# Magus.net
KiCad netlist of a schematic drawn in EAGLE
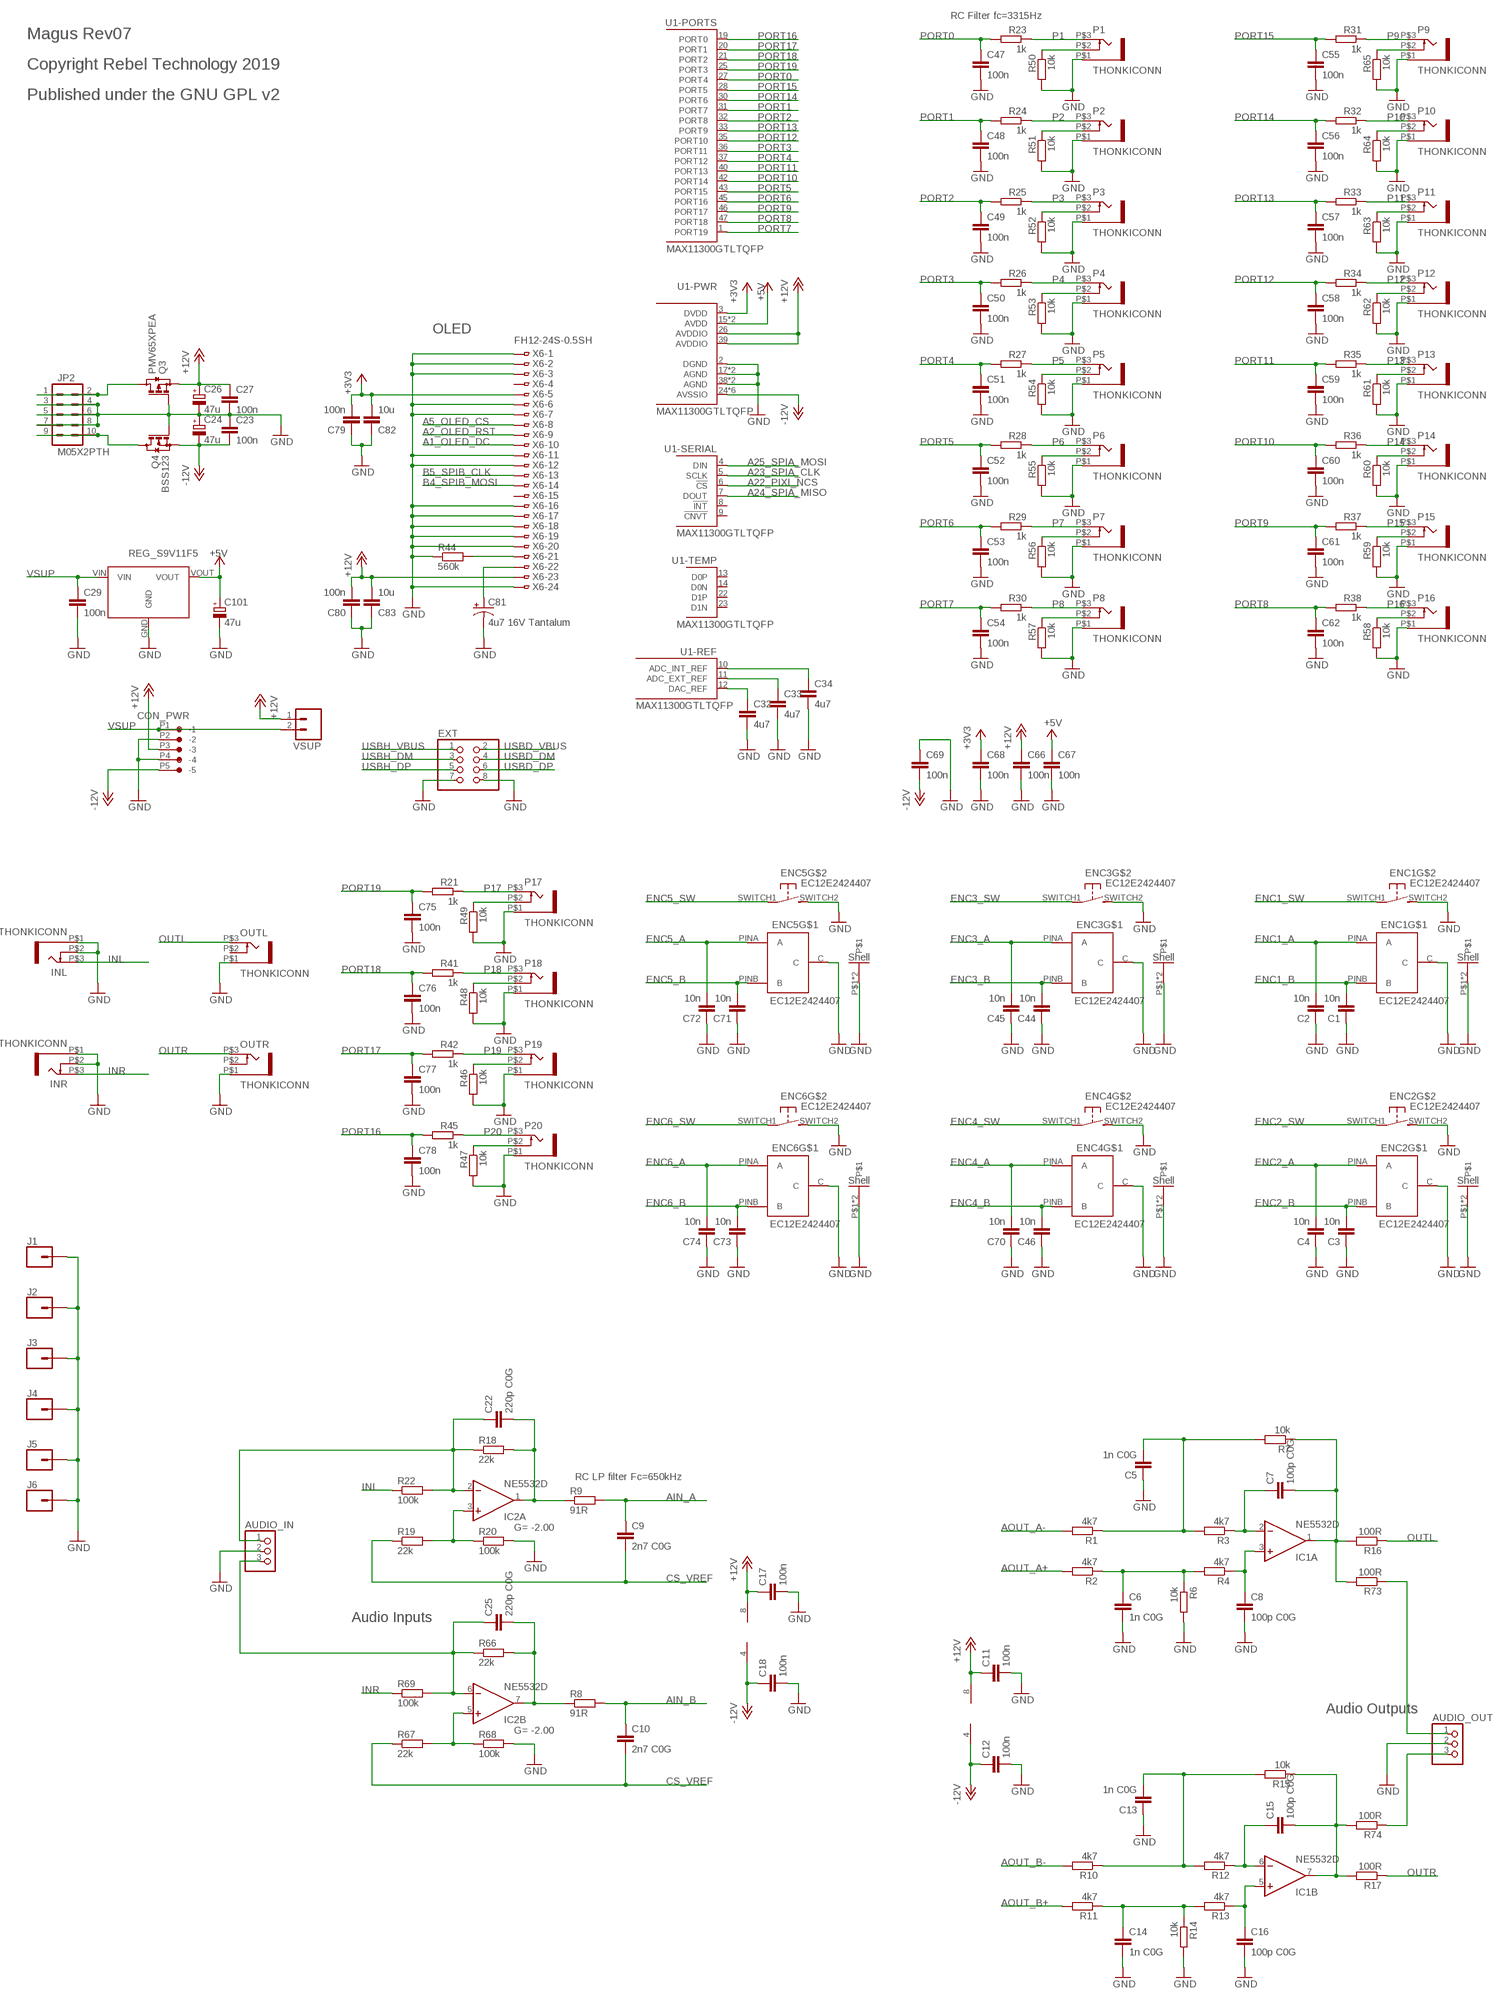
[diagram p0: schematic, sheet 1, part 1 of 2]
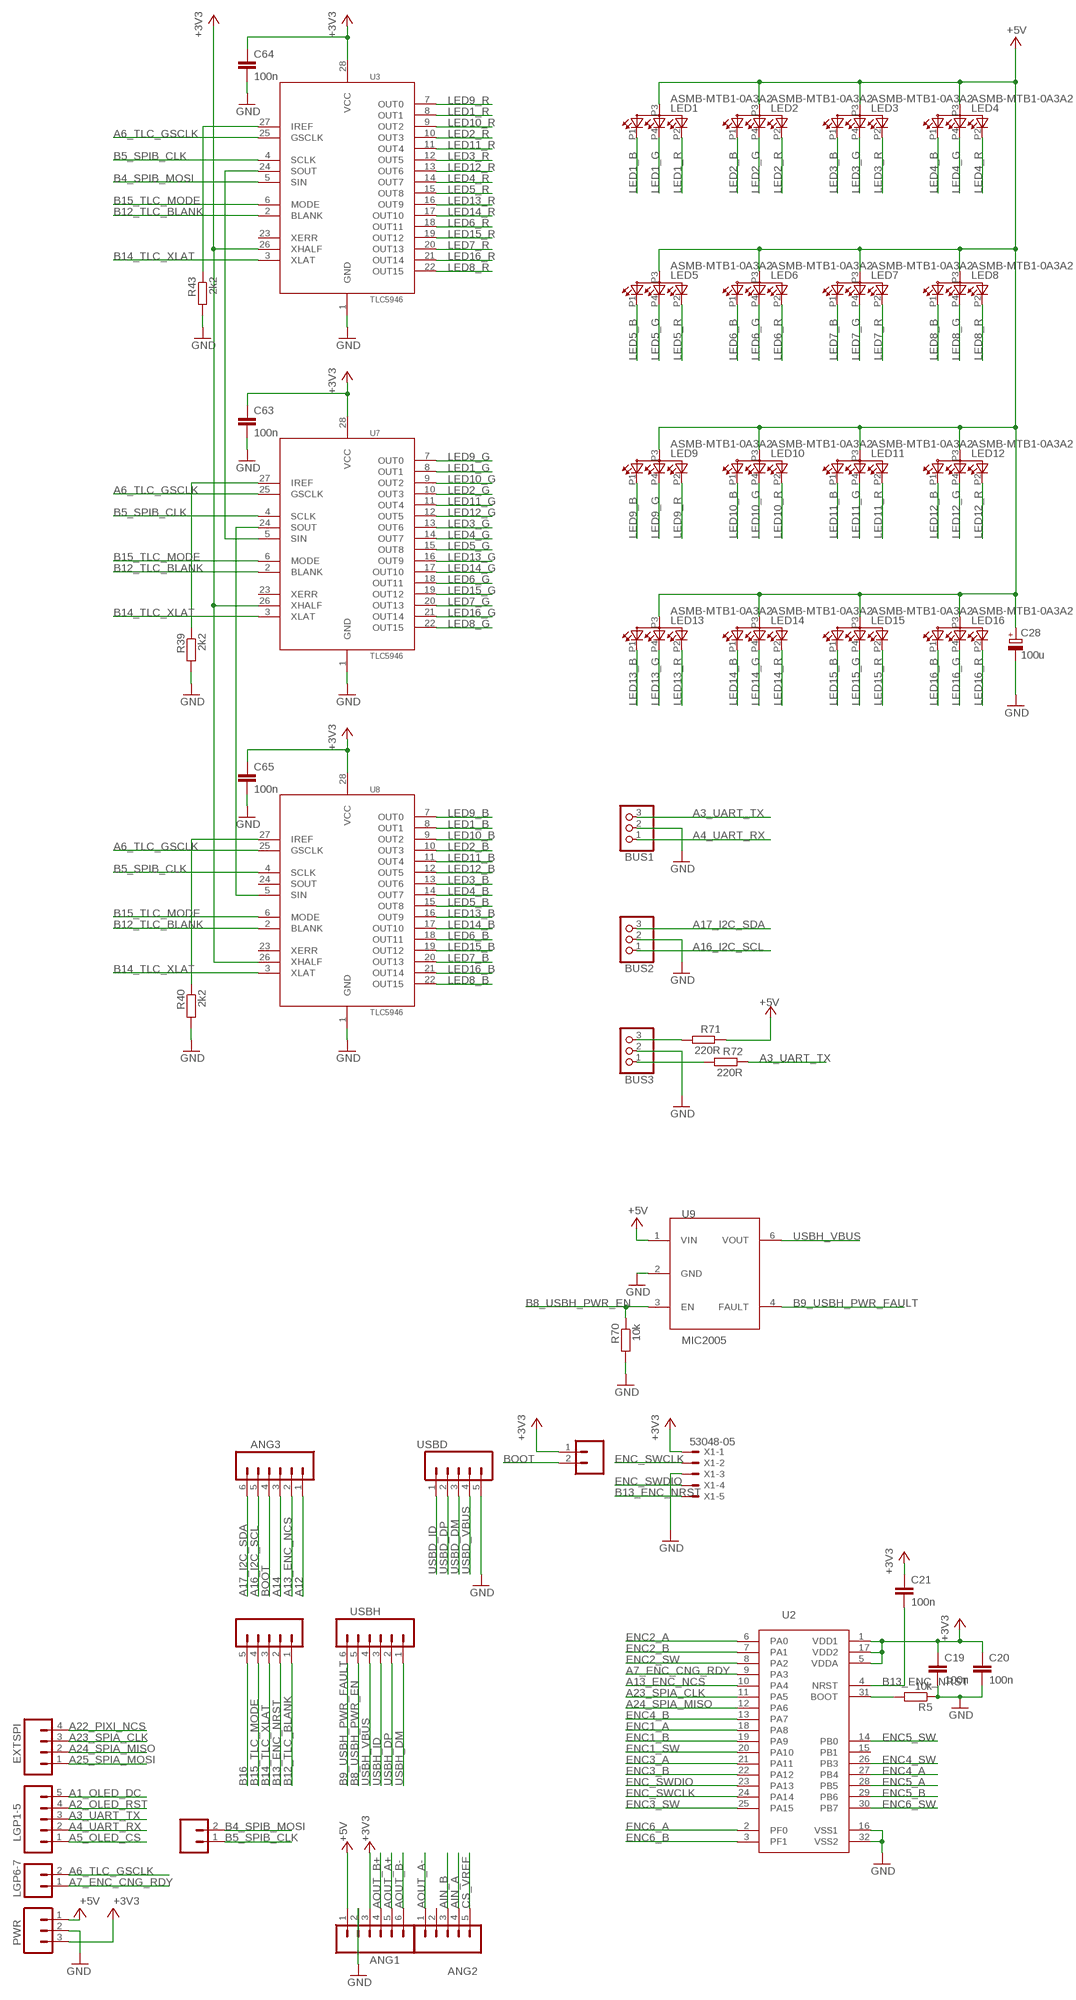
[diagram p1: schematic, sheet 1, part 2 of 2]

(export (version "E")
  (design (tool "Eeschema 10.0.6"))
  (components
    (comp (ref "ANG1")
      (value "M06SIP")
      (footprint "eagle-import:1X06")
      (libsource (lib "eagle-import") (part "M06SIP"))
    )
    (comp (ref "ANG2")
      (value "M05PTH")
      (footprint "eagle-import:1X05")
      (libsource (lib "eagle-import") (part "M05PTH"))
    )
    (comp (ref "ANG3")
      (value "M06SIP")
      (footprint "eagle-import:1X06")
      (libsource (lib "eagle-import") (part "M06SIP"))
    )
    (comp (ref "AUDIO_IN")
      (value "CON-JST-1X03PH-TH")
      (footprint "eagle-import:JST-B3B-PH-KL")
      (libsource (lib "eagle-import") (part "CON-JST-1X03PH-TH"))
    )
    (comp (ref "AUDIO_OUT")
      (value "CON-JST-1X03PH-TH")
      (footprint "eagle-import:JST-B3B-PH-KL")
      (libsource (lib "eagle-import") (part "CON-JST-1X03PH-TH"))
    )
    (comp (ref "BOOT")
      (value "M02PTH")
      (footprint "eagle-import:1X02")
      (libsource (lib "eagle-import") (part "M02PTH"))
    )
    (comp (ref "BUS1")
      (value "CON-JST-1X03PH-TH")
      (footprint "eagle-import:JST-B3B-PH-KL")
      (libsource (lib "eagle-import") (part "CON-JST-1X03PH-TH"))
    )
    (comp (ref "BUS2")
      (value "CON-JST-1X03PH-TH")
      (footprint "eagle-import:JST-B3B-PH-KL")
      (libsource (lib "eagle-import") (part "CON-JST-1X03PH-TH"))
    )
    (comp (ref "BUS3")
      (value "CON-JST-1X03PH-TH")
      (footprint "eagle-import:JST-B3B-PH-KL")
      (libsource (lib "eagle-import") (part "CON-JST-1X03PH-TH"))
    )
    (comp (ref "C1")
      (value "10n")
      (footprint "eagle-import:C0603")
      (libsource (lib "eagle-import") (part "C-EUC0603"))
    )
    (comp (ref "C2")
      (value "10n")
      (footprint "eagle-import:C0603")
      (libsource (lib "eagle-import") (part "C-EUC0603"))
    )
    (comp (ref "C3")
      (value "10n")
      (footprint "eagle-import:C0603")
      (libsource (lib "eagle-import") (part "C-EUC0603"))
    )
    (comp (ref "C4")
      (value "10n")
      (footprint "eagle-import:C0603")
      (libsource (lib "eagle-import") (part "C-EUC0603"))
    )
    (comp (ref "C5")
      (value "1n C0G")
      (footprint "eagle-import:C0603")
      (libsource (lib "eagle-import") (part "C-EUC0603"))
    )
    (comp (ref "C6")
      (value "1n C0G")
      (footprint "eagle-import:C0603")
      (libsource (lib "eagle-import") (part "C-EUC0603"))
    )
    (comp (ref "C7")
      (value "100p C0G")
      (footprint "eagle-import:C0603")
      (libsource (lib "eagle-import") (part "C-EUC0603"))
    )
    (comp (ref "C8")
      (value "100p C0G")
      (footprint "eagle-import:C0603")
      (libsource (lib "eagle-import") (part "C-EUC0603"))
    )
    (comp (ref "C9")
      (value "2n7 C0G")
      (footprint "eagle-import:C0603")
      (libsource (lib "eagle-import") (part "C-EUC0603"))
    )
    (comp (ref "C10")
      (value "2n7 C0G")
      (footprint "eagle-import:C0603")
      (libsource (lib "eagle-import") (part "C-EUC0603"))
    )
    (comp (ref "C11")
      (value "100n")
      (footprint "eagle-import:C0603")
      (libsource (lib "eagle-import") (part "C-EUC0603"))
    )
    (comp (ref "C12")
      (value "100n")
      (footprint "eagle-import:C0603")
      (libsource (lib "eagle-import") (part "C-EUC0603"))
    )
    (comp (ref "C13")
      (value "1n C0G")
      (footprint "eagle-import:C0603")
      (libsource (lib "eagle-import") (part "C-EUC0603"))
    )
    (comp (ref "C14")
      (value "1n C0G")
      (footprint "eagle-import:C0603")
      (libsource (lib "eagle-import") (part "C-EUC0603"))
    )
    (comp (ref "C15")
      (value "100p C0G")
      (footprint "eagle-import:C0603")
      (libsource (lib "eagle-import") (part "C-EUC0603"))
    )
    (comp (ref "C16")
      (value "100p C0G")
      (footprint "eagle-import:C0603")
      (libsource (lib "eagle-import") (part "C-EUC0603"))
    )
    (comp (ref "C17")
      (value "100n")
      (footprint "eagle-import:C0603")
      (libsource (lib "eagle-import") (part "C-EUC0603"))
    )
    (comp (ref "C18")
      (value "100n")
      (footprint "eagle-import:C0603")
      (libsource (lib "eagle-import") (part "C-EUC0603"))
    )
    (comp (ref "C19")
      (value "100n")
      (footprint "eagle-import:C0603")
      (libsource (lib "eagle-import") (part "C-EUC0603"))
    )
    (comp (ref "C20")
      (value "100n")
      (footprint "eagle-import:C0603")
      (libsource (lib "eagle-import") (part "C-EUC0603"))
    )
    (comp (ref "C21")
      (value "100n")
      (footprint "eagle-import:C0603")
      (libsource (lib "eagle-import") (part "C-EUC0603"))
    )
    (comp (ref "C22")
      (value "220p C0G")
      (footprint "eagle-import:C0603")
      (libsource (lib "eagle-import") (part "C-EUC0603"))
    )
    (comp (ref "C23")
      (value "100n")
      (footprint "eagle-import:C0603")
      (libsource (lib "eagle-import") (part "C-EUC0603"))
    )
    (comp (ref "C24")
      (value "47u")
      (footprint "eagle-import:CPOL-5")
      (libsource (lib "eagle-import") (part "CPOL-EU153CLV-0505"))
    )
    (comp (ref "C25")
      (value "220p C0G")
      (footprint "eagle-import:C0603")
      (libsource (lib "eagle-import") (part "C-EUC0603"))
    )
    (comp (ref "C26")
      (value "47u")
      (footprint "eagle-import:CPOL-5")
      (libsource (lib "eagle-import") (part "CPOL-EU153CLV-0505"))
    )
    (comp (ref "C27")
      (value "100n")
      (footprint "eagle-import:C0603")
      (libsource (lib "eagle-import") (part "C-EUC0603"))
    )
    (comp (ref "C28")
      (value "100u")
      (footprint "eagle-import:E5-8,5")
      (libsource (lib "eagle-import") (part "CPOL-EUE5-8.5"))
    )
    (comp (ref "C29")
      (value "100n")
      (footprint "eagle-import:C0603")
      (libsource (lib "eagle-import") (part "C-EUC0603"))
    )
    (comp (ref "C32")
      (value "4u7")
      (footprint "eagle-import:C0603")
      (libsource (lib "eagle-import") (part "C-EUC0603"))
    )
    (comp (ref "C33")
      (value "4u7")
      (footprint "eagle-import:C0603")
      (libsource (lib "eagle-import") (part "C-EUC0603"))
    )
    (comp (ref "C34")
      (value "4u7")
      (footprint "eagle-import:C0603")
      (libsource (lib "eagle-import") (part "C-EUC0603"))
    )
    (comp (ref "C44")
      (value "10n")
      (footprint "eagle-import:C0603")
      (libsource (lib "eagle-import") (part "C-EUC0603"))
    )
    (comp (ref "C45")
      (value "10n")
      (footprint "eagle-import:C0603")
      (libsource (lib "eagle-import") (part "C-EUC0603"))
    )
    (comp (ref "C46")
      (value "10n")
      (footprint "eagle-import:C0603")
      (libsource (lib "eagle-import") (part "C-EUC0603"))
    )
    (comp (ref "C47")
      (value "100n")
      (footprint "eagle-import:C0603")
      (libsource (lib "eagle-import") (part "C-EUC0603"))
    )
    (comp (ref "C48")
      (value "100n")
      (footprint "eagle-import:C0603")
      (libsource (lib "eagle-import") (part "C-EUC0603"))
    )
    (comp (ref "C49")
      (value "100n")
      (footprint "eagle-import:C0603")
      (libsource (lib "eagle-import") (part "C-EUC0603"))
    )
    (comp (ref "C50")
      (value "100n")
      (footprint "eagle-import:C0603")
      (libsource (lib "eagle-import") (part "C-EUC0603"))
    )
    (comp (ref "C51")
      (value "100n")
      (footprint "eagle-import:C0603")
      (libsource (lib "eagle-import") (part "C-EUC0603"))
    )
    (comp (ref "C52")
      (value "100n")
      (footprint "eagle-import:C0603")
      (libsource (lib "eagle-import") (part "C-EUC0603"))
    )
    (comp (ref "C53")
      (value "100n")
      (footprint "eagle-import:C0603")
      (libsource (lib "eagle-import") (part "C-EUC0603"))
    )
    (comp (ref "C54")
      (value "100n")
      (footprint "eagle-import:C0603")
      (libsource (lib "eagle-import") (part "C-EUC0603"))
    )
    (comp (ref "C55")
      (value "100n")
      (footprint "eagle-import:C0603")
      (libsource (lib "eagle-import") (part "C-EUC0603"))
    )
    (comp (ref "C56")
      (value "100n")
      (footprint "eagle-import:C0603")
      (libsource (lib "eagle-import") (part "C-EUC0603"))
    )
    (comp (ref "C57")
      (value "100n")
      (footprint "eagle-import:C0603")
      (libsource (lib "eagle-import") (part "C-EUC0603"))
    )
    (comp (ref "C58")
      (value "100n")
      (footprint "eagle-import:C0603")
      (libsource (lib "eagle-import") (part "C-EUC0603"))
    )
    (comp (ref "C59")
      (value "100n")
      (footprint "eagle-import:C0603")
      (libsource (lib "eagle-import") (part "C-EUC0603"))
    )
    (comp (ref "C60")
      (value "100n")
      (footprint "eagle-import:C0603")
      (libsource (lib "eagle-import") (part "C-EUC0603"))
    )
    (comp (ref "C61")
      (value "100n")
      (footprint "eagle-import:C0603")
      (libsource (lib "eagle-import") (part "C-EUC0603"))
    )
    (comp (ref "C62")
      (value "100n")
      (footprint "eagle-import:C0603")
      (libsource (lib "eagle-import") (part "C-EUC0603"))
    )
    (comp (ref "C63")
      (value "100n")
      (footprint "eagle-import:C0603")
      (libsource (lib "eagle-import") (part "C-EUC0603"))
    )
    (comp (ref "C64")
      (value "100n")
      (footprint "eagle-import:C0603")
      (libsource (lib "eagle-import") (part "C-EUC0603"))
    )
    (comp (ref "C65")
      (value "100n")
      (footprint "eagle-import:C0603")
      (libsource (lib "eagle-import") (part "C-EUC0603"))
    )
    (comp (ref "C66")
      (value "100n")
      (footprint "eagle-import:C0603")
      (libsource (lib "eagle-import") (part "C-EUC0603"))
    )
    (comp (ref "C67")
      (value "100n")
      (footprint "eagle-import:C0603")
      (libsource (lib "eagle-import") (part "C-EUC0603"))
    )
    (comp (ref "C68")
      (value "100n")
      (footprint "eagle-import:C0603")
      (libsource (lib "eagle-import") (part "C-EUC0603"))
    )
    (comp (ref "C69")
      (value "100n")
      (footprint "eagle-import:C0603")
      (libsource (lib "eagle-import") (part "C-EUC0603"))
    )
    (comp (ref "C70")
      (value "10n")
      (footprint "eagle-import:C0603")
      (libsource (lib "eagle-import") (part "C-EUC0603"))
    )
    (comp (ref "C71")
      (value "10n")
      (footprint "eagle-import:C0603")
      (libsource (lib "eagle-import") (part "C-EUC0603"))
    )
    (comp (ref "C72")
      (value "10n")
      (footprint "eagle-import:C0603")
      (libsource (lib "eagle-import") (part "C-EUC0603"))
    )
    (comp (ref "C73")
      (value "10n")
      (footprint "eagle-import:C0603")
      (libsource (lib "eagle-import") (part "C-EUC0603"))
    )
    (comp (ref "C74")
      (value "10n")
      (footprint "eagle-import:C0603")
      (libsource (lib "eagle-import") (part "C-EUC0603"))
    )
    (comp (ref "C75")
      (value "100n")
      (footprint "eagle-import:C0603")
      (libsource (lib "eagle-import") (part "C-EUC0603"))
    )
    (comp (ref "C76")
      (value "100n")
      (footprint "eagle-import:C0603")
      (libsource (lib "eagle-import") (part "C-EUC0603"))
    )
    (comp (ref "C77")
      (value "100n")
      (footprint "eagle-import:C0603")
      (libsource (lib "eagle-import") (part "C-EUC0603"))
    )
    (comp (ref "C78")
      (value "100n")
      (footprint "eagle-import:C0603")
      (libsource (lib "eagle-import") (part "C-EUC0603"))
    )
    (comp (ref "C79")
      (value "100n")
      (footprint "eagle-import:C0603")
      (libsource (lib "eagle-import") (part "C-EUC0603"))
    )
    (comp (ref "C80")
      (value "100n")
      (footprint "eagle-import:C0603")
      (libsource (lib "eagle-import") (part "C-EUC0603"))
    )
    (comp (ref "C81")
      (value "4u7 16V Tantalum")
      (footprint "eagle-import:EIA3216")
      (libsource (lib "eagle-import") (part "CAP_POL1206"))
    )
    (comp (ref "C82")
      (value "10u")
      (footprint "eagle-import:C1206")
      (libsource (lib "eagle-import") (part "C-EUC1206"))
    )
    (comp (ref "C83")
      (value "10u")
      (footprint "eagle-import:C1206")
      (libsource (lib "eagle-import") (part "C-EUC1206"))
    )
    (comp (ref "C101")
      (value "47u")
      (footprint "eagle-import:CPOL-5")
      (libsource (lib "eagle-import") (part "CPOL-EU153CLV-0505"))
    )
    (comp (ref "CON_PWR")
      (value "CON-JST_PH_5W")
      (footprint "eagle-import:CON-JST_PH_5W")
      (libsource (lib "eagle-import") (part "CON-JST_PH_5W"))
    )
    (comp (ref "ENC1")
      (value "EC12E2424407")
      (footprint "eagle-import:EC12E2424407")
      (libsource (lib "eagle-import") (part "EC12E2424407"))
    )
    (comp (ref "ENC2")
      (value "EC12E2424407")
      (footprint "eagle-import:EC12E2424407")
      (libsource (lib "eagle-import") (part "EC12E2424407"))
    )
    (comp (ref "ENC3")
      (value "EC12E2424407")
      (footprint "eagle-import:EC12E2424407")
      (libsource (lib "eagle-import") (part "EC12E2424407"))
    )
    (comp (ref "ENC4")
      (value "EC12E2424407")
      (footprint "eagle-import:EC12E2424407")
      (libsource (lib "eagle-import") (part "EC12E2424407"))
    )
    (comp (ref "ENC5")
      (value "EC12E2424407")
      (footprint "eagle-import:EC12E2424407")
      (libsource (lib "eagle-import") (part "EC12E2424407"))
    )
    (comp (ref "ENC6")
      (value "EC12E2424407")
      (footprint "eagle-import:EC12E2424407")
      (libsource (lib "eagle-import") (part "EC12E2424407"))
    )
    (comp (ref "EXT")
      (value "PINHD-2X4")
      (footprint "eagle-import:2X04")
      (libsource (lib "eagle-import") (part "PINHD-2X4"))
    )
    (comp (ref "EXTSPI")
      (value "M04PTH")
      (footprint "eagle-import:1X04")
      (libsource (lib "eagle-import") (part "M04PTH"))
    )
    (comp (ref "IC1")
      (value "NE5532D")
      (footprint "eagle-import:SO08")
      (libsource (lib "eagle-import") (part "NE5532D"))
    )
    (comp (ref "IC2")
      (value "NE5532D")
      (footprint "eagle-import:SO08")
      (libsource (lib "eagle-import") (part "NE5532D"))
    )
    (comp (ref "INL")
      (value "THONKICONN")
      (footprint "eagle-import:THONKICONN")
      (libsource (lib "eagle-import") (part "THONKICONN"))
    )
    (comp (ref "INR")
      (value "THONKICONN")
      (footprint "eagle-import:THONKICONN")
      (libsource (lib "eagle-import") (part "THONKICONN"))
    )
    (comp (ref "J1")
      (value "CONN_01")
      (footprint "eagle-import:1X01")
      (libsource (lib "eagle-import") (part "CONN_01"))
    )
    (comp (ref "J2")
      (value "CONN_01")
      (footprint "eagle-import:1X01")
      (libsource (lib "eagle-import") (part "CONN_01"))
    )
    (comp (ref "J3")
      (value "CONN_01")
      (footprint "eagle-import:1X01")
      (libsource (lib "eagle-import") (part "CONN_01"))
    )
    (comp (ref "J4")
      (value "CONN_01")
      (footprint "eagle-import:1X01")
      (libsource (lib "eagle-import") (part "CONN_01"))
    )
    (comp (ref "J5")
      (value "CONN_01")
      (footprint "eagle-import:1X01")
      (libsource (lib "eagle-import") (part "CONN_01"))
    )
    (comp (ref "J6")
      (value "CONN_01")
      (footprint "eagle-import:1X01")
      (libsource (lib "eagle-import") (part "CONN_01"))
    )
    (comp (ref "JP2")
      (value "M05X2PTH")
      (footprint "eagle-import:AVR_ICSP")
      (libsource (lib "eagle-import") (part "M05X2PTH"))
    )
    (comp (ref "LED1")
      (value "ASMB-MTB1-0A3A2")
      (footprint "eagle-import:RGB-LED-703-1028")
      (libsource (lib "eagle-import") (part "MULTICOMP_703-1028"))
    )
    (comp (ref "LED2")
      (value "ASMB-MTB1-0A3A2")
      (footprint "eagle-import:RGB-LED-703-1028")
      (libsource (lib "eagle-import") (part "MULTICOMP_703-1028"))
    )
    (comp (ref "LED3")
      (value "ASMB-MTB1-0A3A2")
      (footprint "eagle-import:RGB-LED-703-1028")
      (libsource (lib "eagle-import") (part "MULTICOMP_703-1028"))
    )
    (comp (ref "LED4")
      (value "ASMB-MTB1-0A3A2")
      (footprint "eagle-import:RGB-LED-703-1028")
      (libsource (lib "eagle-import") (part "MULTICOMP_703-1028"))
    )
    (comp (ref "LED5")
      (value "ASMB-MTB1-0A3A2")
      (footprint "eagle-import:RGB-LED-703-1028")
      (libsource (lib "eagle-import") (part "MULTICOMP_703-1028"))
    )
    (comp (ref "LED6")
      (value "ASMB-MTB1-0A3A2")
      (footprint "eagle-import:RGB-LED-703-1028")
      (libsource (lib "eagle-import") (part "MULTICOMP_703-1028"))
    )
    (comp (ref "LED7")
      (value "ASMB-MTB1-0A3A2")
      (footprint "eagle-import:RGB-LED-703-1028")
      (libsource (lib "eagle-import") (part "MULTICOMP_703-1028"))
    )
    (comp (ref "LED8")
      (value "ASMB-MTB1-0A3A2")
      (footprint "eagle-import:RGB-LED-703-1028")
      (libsource (lib "eagle-import") (part "MULTICOMP_703-1028"))
    )
    (comp (ref "LED9")
      (value "ASMB-MTB1-0A3A2")
      (footprint "eagle-import:RGB-LED-703-1028")
      (libsource (lib "eagle-import") (part "MULTICOMP_703-1028"))
    )
    (comp (ref "LED10")
      (value "ASMB-MTB1-0A3A2")
      (footprint "eagle-import:RGB-LED-703-1028")
      (libsource (lib "eagle-import") (part "MULTICOMP_703-1028"))
    )
    (comp (ref "LED11")
      (value "ASMB-MTB1-0A3A2")
      (footprint "eagle-import:RGB-LED-703-1028")
      (libsource (lib "eagle-import") (part "MULTICOMP_703-1028"))
    )
    (comp (ref "LED12")
      (value "ASMB-MTB1-0A3A2")
      (footprint "eagle-import:RGB-LED-703-1028")
      (libsource (lib "eagle-import") (part "MULTICOMP_703-1028"))
    )
    (comp (ref "LED13")
      (value "ASMB-MTB1-0A3A2")
      (footprint "eagle-import:RGB-LED-703-1028")
      (libsource (lib "eagle-import") (part "MULTICOMP_703-1028"))
    )
    (comp (ref "LED14")
      (value "ASMB-MTB1-0A3A2")
      (footprint "eagle-import:RGB-LED-703-1028")
      (libsource (lib "eagle-import") (part "MULTICOMP_703-1028"))
    )
    (comp (ref "LED15")
      (value "ASMB-MTB1-0A3A2")
      (footprint "eagle-import:RGB-LED-703-1028")
      (libsource (lib "eagle-import") (part "MULTICOMP_703-1028"))
    )
    (comp (ref "LED16")
      (value "ASMB-MTB1-0A3A2")
      (footprint "eagle-import:RGB-LED-703-1028")
      (libsource (lib "eagle-import") (part "MULTICOMP_703-1028"))
    )
    (comp (ref "LGP1-5")
      (value "M05PTH")
      (footprint "eagle-import:1X05")
      (libsource (lib "eagle-import") (part "M05PTH"))
    )
    (comp (ref "LGP6-1")
      (value "M02PTH")
      (footprint "eagle-import:1X02")
      (libsource (lib "eagle-import") (part "M02PTH"))
    )
    (comp (ref "LGP6-7")
      (value "M02PTH")
      (footprint "eagle-import:1X02")
      (libsource (lib "eagle-import") (part "M02PTH"))
    )
    (comp (ref "OUTL")
      (value "THONKICONN")
      (footprint "eagle-import:THONKICONN")
      (libsource (lib "eagle-import") (part "THONKICONN"))
    )
    (comp (ref "OUTR")
      (value "THONKICONN")
      (footprint "eagle-import:THONKICONN")
      (libsource (lib "eagle-import") (part "THONKICONN"))
    )
    (comp (ref "P1")
      (value "THONKICONN")
      (footprint "eagle-import:THONKICONN")
      (libsource (lib "eagle-import") (part "THONKICONN"))
    )
    (comp (ref "P2")
      (value "THONKICONN")
      (footprint "eagle-import:THONKICONN")
      (libsource (lib "eagle-import") (part "THONKICONN"))
    )
    (comp (ref "P3")
      (value "THONKICONN")
      (footprint "eagle-import:THONKICONN")
      (libsource (lib "eagle-import") (part "THONKICONN"))
    )
    (comp (ref "P4")
      (value "THONKICONN")
      (footprint "eagle-import:THONKICONN")
      (libsource (lib "eagle-import") (part "THONKICONN"))
    )
    (comp (ref "P5")
      (value "THONKICONN")
      (footprint "eagle-import:THONKICONN")
      (libsource (lib "eagle-import") (part "THONKICONN"))
    )
    (comp (ref "P6")
      (value "THONKICONN")
      (footprint "eagle-import:THONKICONN")
      (libsource (lib "eagle-import") (part "THONKICONN"))
    )
    (comp (ref "P7")
      (value "THONKICONN")
      (footprint "eagle-import:THONKICONN")
      (libsource (lib "eagle-import") (part "THONKICONN"))
    )
    (comp (ref "P8")
      (value "THONKICONN")
      (footprint "eagle-import:THONKICONN")
      (libsource (lib "eagle-import") (part "THONKICONN"))
    )
    (comp (ref "P9")
      (value "THONKICONN")
      (footprint "eagle-import:THONKICONN")
      (libsource (lib "eagle-import") (part "THONKICONN"))
    )
    (comp (ref "P10")
      (value "THONKICONN")
      (footprint "eagle-import:THONKICONN")
      (libsource (lib "eagle-import") (part "THONKICONN"))
    )
    (comp (ref "P11")
      (value "THONKICONN")
      (footprint "eagle-import:THONKICONN")
      (libsource (lib "eagle-import") (part "THONKICONN"))
    )
    (comp (ref "P12")
      (value "THONKICONN")
      (footprint "eagle-import:THONKICONN")
      (libsource (lib "eagle-import") (part "THONKICONN"))
    )
    (comp (ref "P13")
      (value "THONKICONN")
      (footprint "eagle-import:THONKICONN")
      (libsource (lib "eagle-import") (part "THONKICONN"))
    )
    (comp (ref "P14")
      (value "THONKICONN")
      (footprint "eagle-import:THONKICONN")
      (libsource (lib "eagle-import") (part "THONKICONN"))
    )
    (comp (ref "P15")
      (value "THONKICONN")
      (footprint "eagle-import:THONKICONN")
      (libsource (lib "eagle-import") (part "THONKICONN"))
    )
    (comp (ref "P16")
      (value "THONKICONN")
      (footprint "eagle-import:THONKICONN")
      (libsource (lib "eagle-import") (part "THONKICONN"))
    )
    (comp (ref "P17")
      (value "THONKICONN")
      (footprint "eagle-import:THONKICONN")
      (libsource (lib "eagle-import") (part "THONKICONN"))
    )
    (comp (ref "P18")
      (value "THONKICONN")
      (footprint "eagle-import:THONKICONN")
      (libsource (lib "eagle-import") (part "THONKICONN"))
    )
    (comp (ref "P19")
      (value "THONKICONN")
      (footprint "eagle-import:THONKICONN")
      (libsource (lib "eagle-import") (part "THONKICONN"))
    )
    (comp (ref "P20")
      (value "THONKICONN")
      (footprint "eagle-import:THONKICONN")
      (libsource (lib "eagle-import") (part "THONKICONN"))
    )
    (comp (ref "PWR")
      (value "M03PTH")
      (footprint "eagle-import:1X03")
      (libsource (lib "eagle-import") (part "M03PTH"))
    )
    (comp (ref "Q3")
      (value "PMV65XPEA")
      (footprint "eagle-import:SOT23")
      (libsource (lib "eagle-import") (part "BSS84"))
    )
    (comp (ref "Q4")
      (value "BSS123")
      (footprint "eagle-import:SOT23")
      (libsource (lib "eagle-import") (part "BSS123"))
    )
    (comp (ref "R1")
      (value "4k7")
      (footprint "eagle-import:0603")
      (libsource (lib "eagle-import") (part "R-EU_0603"))
    )
    (comp (ref "R2")
      (value "4k7")
      (footprint "eagle-import:0603")
      (libsource (lib "eagle-import") (part "R-EU_0603"))
    )
    (comp (ref "R3")
      (value "4k7")
      (footprint "eagle-import:0603")
      (libsource (lib "eagle-import") (part "R-EU_0603"))
    )
    (comp (ref "R4")
      (value "4k7")
      (footprint "eagle-import:0603")
      (libsource (lib "eagle-import") (part "R-EU_0603"))
    )
    (comp (ref "R5")
      (value "10k")
      (footprint "eagle-import:0603")
      (libsource (lib "eagle-import") (part "R-EU_0603"))
    )
    (comp (ref "R6")
      (value "10k")
      (footprint "eagle-import:0603")
      (libsource (lib "eagle-import") (part "R-EU_0603"))
    )
    (comp (ref "R7")
      (value "10k")
      (footprint "eagle-import:0603")
      (libsource (lib "eagle-import") (part "R-EU_0603"))
    )
    (comp (ref "R8")
      (value "91R")
      (footprint "eagle-import:0603")
      (libsource (lib "eagle-import") (part "R-EU_0603"))
    )
    (comp (ref "R9")
      (value "91R")
      (footprint "eagle-import:0603")
      (libsource (lib "eagle-import") (part "R-EU_0603"))
    )
    (comp (ref "R10")
      (value "4k7")
      (footprint "eagle-import:0603")
      (libsource (lib "eagle-import") (part "R-EU_0603"))
    )
    (comp (ref "R11")
      (value "4k7")
      (footprint "eagle-import:0603")
      (libsource (lib "eagle-import") (part "R-EU_0603"))
    )
    (comp (ref "R12")
      (value "4k7")
      (footprint "eagle-import:0603")
      (libsource (lib "eagle-import") (part "R-EU_0603"))
    )
    (comp (ref "R13")
      (value "4k7")
      (footprint "eagle-import:0603")
      (libsource (lib "eagle-import") (part "R-EU_0603"))
    )
    (comp (ref "R14")
      (value "10k")
      (footprint "eagle-import:0603")
      (libsource (lib "eagle-import") (part "R-EU_0603"))
    )
    (comp (ref "R15")
      (value "10k")
      (footprint "eagle-import:0603")
      (libsource (lib "eagle-import") (part "R-EU_0603"))
    )
    (comp (ref "R16")
      (value "100R")
      (footprint "eagle-import:0603")
      (libsource (lib "eagle-import") (part "R-EU_0603"))
    )
    (comp (ref "R17")
      (value "100R")
      (footprint "eagle-import:0603")
      (libsource (lib "eagle-import") (part "R-EU_0603"))
    )
    (comp (ref "R18")
      (value "22k")
      (footprint "eagle-import:0603")
      (libsource (lib "eagle-import") (part "R-EU_0603"))
    )
    (comp (ref "R19")
      (value "22k")
      (footprint "eagle-import:0603")
      (libsource (lib "eagle-import") (part "R-EU_0603"))
    )
    (comp (ref "R20")
      (value "100k")
      (footprint "eagle-import:0603")
      (libsource (lib "eagle-import") (part "R-EU_0603"))
    )
    (comp (ref "R21")
      (value "1k")
      (footprint "eagle-import:0603")
      (libsource (lib "eagle-import") (part "R-EU_0603"))
    )
    (comp (ref "R22")
      (value "100k")
      (footprint "eagle-import:0603")
      (libsource (lib "eagle-import") (part "R-EU_0603"))
    )
    (comp (ref "R23")
      (value "1k")
      (footprint "eagle-import:0603")
      (libsource (lib "eagle-import") (part "R-EU_0603"))
    )
    (comp (ref "R24")
      (value "1k")
      (footprint "eagle-import:0603")
      (libsource (lib "eagle-import") (part "R-EU_0603"))
    )
    (comp (ref "R25")
      (value "1k")
      (footprint "eagle-import:0603")
      (libsource (lib "eagle-import") (part "R-EU_0603"))
    )
    (comp (ref "R26")
      (value "1k")
      (footprint "eagle-import:0603")
      (libsource (lib "eagle-import") (part "R-EU_0603"))
    )
    (comp (ref "R27")
      (value "1k")
      (footprint "eagle-import:0603")
      (libsource (lib "eagle-import") (part "R-EU_0603"))
    )
    (comp (ref "R28")
      (value "1k")
      (footprint "eagle-import:0603")
      (libsource (lib "eagle-import") (part "R-EU_0603"))
    )
    (comp (ref "R29")
      (value "1k")
      (footprint "eagle-import:0603")
      (libsource (lib "eagle-import") (part "R-EU_0603"))
    )
    (comp (ref "R30")
      (value "1k")
      (footprint "eagle-import:0603")
      (libsource (lib "eagle-import") (part "R-EU_0603"))
    )
    (comp (ref "R31")
      (value "1k")
      (footprint "eagle-import:0603")
      (libsource (lib "eagle-import") (part "R-EU_0603"))
    )
    (comp (ref "R32")
      (value "1k")
      (footprint "eagle-import:0603")
      (libsource (lib "eagle-import") (part "R-EU_0603"))
    )
    (comp (ref "R33")
      (value "1k")
      (footprint "eagle-import:0603")
      (libsource (lib "eagle-import") (part "R-EU_0603"))
    )
    (comp (ref "R34")
      (value "1k")
      (footprint "eagle-import:0603")
      (libsource (lib "eagle-import") (part "R-EU_0603"))
    )
    (comp (ref "R35")
      (value "1k")
      (footprint "eagle-import:0603")
      (libsource (lib "eagle-import") (part "R-EU_0603"))
    )
    (comp (ref "R36")
      (value "1k")
      (footprint "eagle-import:0603")
      (libsource (lib "eagle-import") (part "R-EU_0603"))
    )
    (comp (ref "R37")
      (value "1k")
      (footprint "eagle-import:0603")
      (libsource (lib "eagle-import") (part "R-EU_0603"))
    )
    (comp (ref "R38")
      (value "1k")
      (footprint "eagle-import:0603")
      (libsource (lib "eagle-import") (part "R-EU_0603"))
    )
    (comp (ref "R39")
      (value "2k2")
      (footprint "eagle-import:0603")
      (libsource (lib "eagle-import") (part "R-EU_0603"))
    )
    (comp (ref "R40")
      (value "2k2")
      (footprint "eagle-import:0603")
      (libsource (lib "eagle-import") (part "R-EU_0603"))
    )
    (comp (ref "R41")
      (value "1k")
      (footprint "eagle-import:0603")
      (libsource (lib "eagle-import") (part "R-EU_0603"))
    )
    (comp (ref "R42")
      (value "1k")
      (footprint "eagle-import:0603")
      (libsource (lib "eagle-import") (part "R-EU_0603"))
    )
    (comp (ref "R43")
      (value "2k2")
      (footprint "eagle-import:0603")
      (libsource (lib "eagle-import") (part "R-EU_0603"))
    )
    (comp (ref "R44")
      (value "560k")
      (footprint "eagle-import:0603")
      (libsource (lib "eagle-import") (part "R-EU_0603"))
    )
    (comp (ref "R45")
      (value "1k")
      (footprint "eagle-import:0603")
      (libsource (lib "eagle-import") (part "R-EU_0603"))
    )
    (comp (ref "R46")
      (value "10k")
      (footprint "eagle-import:0603")
      (libsource (lib "eagle-import") (part "R-EU_0603"))
    )
    (comp (ref "R47")
      (value "10k")
      (footprint "eagle-import:0603")
      (libsource (lib "eagle-import") (part "R-EU_0603"))
    )
    (comp (ref "R48")
      (value "10k")
      (footprint "eagle-import:0603")
      (libsource (lib "eagle-import") (part "R-EU_0603"))
    )
    (comp (ref "R49")
      (value "10k")
      (footprint "eagle-import:0603")
      (libsource (lib "eagle-import") (part "R-EU_0603"))
    )
    (comp (ref "R50")
      (value "10k")
      (footprint "eagle-import:0603")
      (libsource (lib "eagle-import") (part "R-EU_0603"))
    )
    (comp (ref "R51")
      (value "10k")
      (footprint "eagle-import:0603")
      (libsource (lib "eagle-import") (part "R-EU_0603"))
    )
    (comp (ref "R52")
      (value "10k")
      (footprint "eagle-import:0603")
      (libsource (lib "eagle-import") (part "R-EU_0603"))
    )
    (comp (ref "R53")
      (value "10k")
      (footprint "eagle-import:0603")
      (libsource (lib "eagle-import") (part "R-EU_0603"))
    )
    (comp (ref "R54")
      (value "10k")
      (footprint "eagle-import:0603")
      (libsource (lib "eagle-import") (part "R-EU_0603"))
    )
    (comp (ref "R55")
      (value "10k")
      (footprint "eagle-import:0603")
      (libsource (lib "eagle-import") (part "R-EU_0603"))
    )
    (comp (ref "R56")
      (value "10k")
      (footprint "eagle-import:0603")
      (libsource (lib "eagle-import") (part "R-EU_0603"))
    )
    (comp (ref "R57")
      (value "10k")
      (footprint "eagle-import:0603")
      (libsource (lib "eagle-import") (part "R-EU_0603"))
    )
    (comp (ref "R58")
      (value "10k")
      (footprint "eagle-import:0603")
      (libsource (lib "eagle-import") (part "R-EU_0603"))
    )
    (comp (ref "R59")
      (value "10k")
      (footprint "eagle-import:0603")
      (libsource (lib "eagle-import") (part "R-EU_0603"))
    )
    (comp (ref "R60")
      (value "10k")
      (footprint "eagle-import:0603")
      (libsource (lib "eagle-import") (part "R-EU_0603"))
    )
    (comp (ref "R61")
      (value "10k")
      (footprint "eagle-import:0603")
      (libsource (lib "eagle-import") (part "R-EU_0603"))
    )
    (comp (ref "R62")
      (value "10k")
      (footprint "eagle-import:0603")
      (libsource (lib "eagle-import") (part "R-EU_0603"))
    )
    (comp (ref "R63")
      (value "10k")
      (footprint "eagle-import:0603")
      (libsource (lib "eagle-import") (part "R-EU_0603"))
    )
    (comp (ref "R64")
      (value "10k")
      (footprint "eagle-import:0603")
      (libsource (lib "eagle-import") (part "R-EU_0603"))
    )
    (comp (ref "R65")
      (value "10k")
      (footprint "eagle-import:0603")
      (libsource (lib "eagle-import") (part "R-EU_0603"))
    )
    (comp (ref "R66")
      (value "22k")
      (footprint "eagle-import:0603")
      (libsource (lib "eagle-import") (part "R-EU_0603"))
    )
    (comp (ref "R67")
      (value "22k")
      (footprint "eagle-import:0603")
      (libsource (lib "eagle-import") (part "R-EU_0603"))
    )
    (comp (ref "R68")
      (value "100k")
      (footprint "eagle-import:0603")
      (libsource (lib "eagle-import") (part "R-EU_0603"))
    )
    (comp (ref "R69")
      (value "100k")
      (footprint "eagle-import:0603")
      (libsource (lib "eagle-import") (part "R-EU_0603"))
    )
    (comp (ref "R70")
      (value "10k")
      (footprint "eagle-import:0603")
      (libsource (lib "eagle-import") (part "R-EU_0603"))
    )
    (comp (ref "R71")
      (value "220R")
      (footprint "eagle-import:0603")
      (libsource (lib "eagle-import") (part "R-EU_0603"))
    )
    (comp (ref "R72")
      (value "220R")
      (footprint "eagle-import:0603")
      (libsource (lib "eagle-import") (part "R-EU_0603"))
    )
    (comp (ref "R73")
      (value "100R")
      (footprint "eagle-import:0603")
      (libsource (lib "eagle-import") (part "R-EU_0603"))
    )
    (comp (ref "R74")
      (value "100R")
      (footprint "eagle-import:0603")
      (libsource (lib "eagle-import") (part "R-EU_0603"))
    )
    (comp (ref "U1")
      (value "MAX11300GTLTQFP")
      (footprint "eagle-import:TQFP48")
      (libsource (lib "eagle-import") (part "MAX11300GTLTQFP"))
    )
    (comp (ref "U2")
      (value "STM32F051K4T6")
      (footprint "eagle-import:LQFP32-7X7")
      (libsource (lib "eagle-import") (part "STM32F051K4T6"))
    )
    (comp (ref "U3")
      (value "TLC5946")
      (footprint "eagle-import:TSSOP28")
      (libsource (lib "eagle-import") (part "TLC5946"))
    )
    (comp (ref "U4")
      (value "REG_S9V11F5")
      (footprint "eagle-import:REG_S9V11F5")
      (libsource (lib "eagle-import") (part "REG_S9V11F5"))
    )
    (comp (ref "U7")
      (value "TLC5946")
      (footprint "eagle-import:TSSOP28")
      (libsource (lib "eagle-import") (part "TLC5946"))
    )
    (comp (ref "U8")
      (value "TLC5946")
      (footprint "eagle-import:TSSOP28")
      (libsource (lib "eagle-import") (part "TLC5946"))
    )
    (comp (ref "U9")
      (value "MIC2005")
      (footprint "eagle-import:SOT23-6")
      (libsource (lib "eagle-import") (part "MIC2005"))
    )
    (comp (ref "USB1")
      (value "M05PTH")
      (footprint "eagle-import:1X05")
      (libsource (lib "eagle-import") (part "M05PTH"))
    )
    (comp (ref "USBD")
      (value "M05PTH")
      (footprint "eagle-import:1X05")
      (libsource (lib "eagle-import") (part "M05PTH"))
    )
    (comp (ref "USBH")
      (value "M06SIP")
      (footprint "eagle-import:1X06")
      (libsource (lib "eagle-import") (part "M06SIP"))
    )
    (comp (ref "VSUP")
      (value "M02PTH")
      (footprint "eagle-import:1X02")
      (libsource (lib "eagle-import") (part "M02PTH"))
    )
    (comp (ref "X1")
      (value "53048-05")
      (footprint "eagle-import:53048-05")
      (fields (field (name "MF") "MOLEX") (field (name "MPN") "53048-0510"))
      (libsource (lib "eagle-import") (part "53?-05048"))
    )
    (comp (ref "X6")
      (value "FH12-24S-0.5SH")
      (footprint "eagle-import:FH12-24S-0.5SH")
      (fields (field (name "MPN") "FH12-24S-0.5SH(55)"))
      (libsource (lib "eagle-import") (part "FH12-24S-0.5SH"))
    )
  )
  (nets
    (net (code "1") (name "+3V3") (class "Default")
      (node (ref "ANG1") (pin "3") (pinfunction "3_3") (pintype "passive"))
      (node (ref "BOOT") (pin "1") (pinfunction "1_1") (pintype "passive"))
      (node (ref "C19") (pin "1") (pinfunction "1_1") (pintype "passive"))
      (node (ref "C20") (pin "1") (pinfunction "1_1") (pintype "passive"))
      (node (ref "C21") (pin "1") (pinfunction "1_1") (pintype "passive"))
      (node (ref "C63") (pin "1") (pinfunction "1_1") (pintype "passive"))
      (node (ref "C64") (pin "1") (pinfunction "1_1") (pintype "passive"))
      (node (ref "C65") (pin "1") (pinfunction "1_1") (pintype "passive"))
      (node (ref "C68") (pin "1") (pinfunction "1_1") (pintype "passive"))
      (node (ref "C79") (pin "2") (pinfunction "2_2") (pintype "passive"))
      (node (ref "C82") (pin "2") (pinfunction "2_2") (pintype "passive"))
      (node (ref "PWR") (pin "3") (pinfunction "3_3") (pintype "passive"))
      (node (ref "U1") (pin "3") (pinfunction "DVDD_3") (pintype "bidirectional"))
      (node (ref "U2") (pin "1") (pinfunction "VDD1_1") (pintype "power_in"))
      (node (ref "U2") (pin "17") (pinfunction "VDD2_17") (pintype "power_in"))
      (node (ref "U2") (pin "5") (pinfunction "VDDA_5") (pintype "power_in"))
      (node (ref "U3") (pin "26") (pinfunction "XHALF_26") (pintype "bidirectional"))
      (node (ref "U3") (pin "28") (pinfunction "VCC_28") (pintype "bidirectional"))
      (node (ref "U7") (pin "26") (pinfunction "XHALF_26") (pintype "bidirectional"))
      (node (ref "U7") (pin "28") (pinfunction "VCC_28") (pintype "bidirectional"))
      (node (ref "U8") (pin "26") (pinfunction "XHALF_26") (pintype "bidirectional"))
      (node (ref "U8") (pin "28") (pinfunction "VCC_28") (pintype "bidirectional"))
      (node (ref "X1") (pin "1") (pinfunction "S_1") (pintype "passive"))
      (node (ref "X6") (pin "5") (pinfunction "1_5") (pintype "passive"))
    )
    (net (code "2") (name "+5V") (class "Default")
      (node (ref "ANG1") (pin "1") (pinfunction "1_1") (pintype "passive"))
      (node (ref "C101") (pin "+") (pinfunction "+_+") (pintype "passive"))
      (node (ref "C28") (pin "+") (pinfunction "+_+") (pintype "passive"))
      (node (ref "C67") (pin "1") (pinfunction "1_1") (pintype "passive"))
      (node (ref "LED1") (pin "P3") (pinfunction "A_P3") (pintype "passive"))
      (node (ref "LED10") (pin "P3") (pinfunction "A_P3") (pintype "passive"))
      (node (ref "LED11") (pin "P3") (pinfunction "A_P3") (pintype "passive"))
      (node (ref "LED12") (pin "P3") (pinfunction "A_P3") (pintype "passive"))
      (node (ref "LED13") (pin "P3") (pinfunction "A_P3") (pintype "passive"))
      (node (ref "LED14") (pin "P3") (pinfunction "A_P3") (pintype "passive"))
      (node (ref "LED15") (pin "P3") (pinfunction "A_P3") (pintype "passive"))
      (node (ref "LED16") (pin "P3") (pinfunction "A_P3") (pintype "passive"))
      (node (ref "LED2") (pin "P3") (pinfunction "A_P3") (pintype "passive"))
      (node (ref "LED3") (pin "P3") (pinfunction "A_P3") (pintype "passive"))
      (node (ref "LED4") (pin "P3") (pinfunction "A_P3") (pintype "passive"))
      (node (ref "LED5") (pin "P3") (pinfunction "A_P3") (pintype "passive"))
      (node (ref "LED6") (pin "P3") (pinfunction "A_P3") (pintype "passive"))
      (node (ref "LED7") (pin "P3") (pinfunction "A_P3") (pintype "passive"))
      (node (ref "LED8") (pin "P3") (pinfunction "A_P3") (pintype "passive"))
      (node (ref "LED9") (pin "P3") (pinfunction "A_P3") (pintype "passive"))
      (node (ref "PWR") (pin "1") (pinfunction "1_1") (pintype "passive"))
      (node (ref "R71") (pin "1") (pinfunction "1_1") (pintype "passive"))
      (node (ref "U1") (pin "15") (pinfunction "AVDD_15") (pintype "bidirectional"))
      (node (ref "U1") (pin "16") (pinfunction "AVDD_16") (pintype "bidirectional"))
      (node (ref "U4") (pin "VOUT") (pinfunction "VOUT_VOUT") (pintype "output"))
      (node (ref "U9") (pin "1") (pinfunction "VIN_1") (pintype "power_in"))
    )
    (net (code "3") (name "+12V") (class "Default")
      (node (ref "C11") (pin "1") (pinfunction "1_1") (pintype "passive"))
      (node (ref "C17") (pin "1") (pinfunction "1_1") (pintype "passive"))
      (node (ref "C26") (pin "+") (pinfunction "+_+") (pintype "passive"))
      (node (ref "C27") (pin "1") (pinfunction "1_1") (pintype "passive"))
      (node (ref "C66") (pin "1") (pinfunction "1_1") (pintype "passive"))
      (node (ref "C80") (pin "2") (pinfunction "2_2") (pintype "passive"))
      (node (ref "C83") (pin "2") (pinfunction "2_2") (pintype "passive"))
      (node (ref "CON_PWR") (pin "P3") (pinfunction "-3_P3") (pintype "bidirectional"))
      (node (ref "IC1") (pin "8") (pinfunction "V+_8") (pintype "power_in"))
      (node (ref "IC2") (pin "8") (pinfunction "V+_8") (pintype "power_in"))
      (node (ref "Q3") (pin "2") (pinfunction "S_2") (pintype "passive"))
      (node (ref "U1") (pin "26") (pinfunction "AVDDIO_26") (pintype "bidirectional"))
      (node (ref "U1") (pin "39") (pinfunction "AVDDIO_39") (pintype "bidirectional"))
      (node (ref "VSUP") (pin "1") (pinfunction "1_1") (pintype "passive"))
      (node (ref "X6") (pin "23") (pinfunction "1_23") (pintype "passive"))
    )
    (net (code "4") (name "-12V") (class "Default")
      (node (ref "C12") (pin "1") (pinfunction "1_1") (pintype "passive"))
      (node (ref "C18") (pin "1") (pinfunction "1_1") (pintype "passive"))
      (node (ref "C23") (pin "2") (pinfunction "2_2") (pintype "passive"))
      (node (ref "C24") (pin "-") (pinfunction "-_-") (pintype "passive"))
      (node (ref "C69") (pin "2") (pinfunction "2_2") (pintype "passive"))
      (node (ref "CON_PWR") (pin "P5") (pinfunction "-5_P5") (pintype "bidirectional"))
      (node (ref "IC1") (pin "4") (pinfunction "V-_4") (pintype "power_in"))
      (node (ref "IC2") (pin "4") (pinfunction "V-_4") (pintype "power_in"))
      (node (ref "Q4") (pin "2") (pinfunction "S_2") (pintype "passive"))
      (node (ref "U1") (pin "24") (pinfunction "AVSSIO_24") (pintype "bidirectional"))
      (node (ref "U1") (pin "29") (pinfunction "AVSSIO_29") (pintype "bidirectional"))
      (node (ref "U1") (pin "34") (pinfunction "AVSSIO_34") (pintype "bidirectional"))
      (node (ref "U1") (pin "41") (pinfunction "AVSSIO_41") (pintype "bidirectional"))
      (node (ref "U1") (pin "44") (pinfunction "AVSSIO_44") (pintype "bidirectional"))
      (node (ref "U1") (pin "48") (pinfunction "AVSSIO_48") (pintype "bidirectional"))
    )
    (net (code "5") (name "/A1_OLED_DC") (class "Default")
      (node (ref "LGP1-5") (pin "5") (pinfunction "5_5") (pintype "passive"))
      (node (ref "X6") (pin "10") (pinfunction "1_10") (pintype "passive"))
    )
    (net (code "6") (name "/A2_OLED_RST") (class "Default")
      (node (ref "LGP1-5") (pin "4") (pinfunction "4_4") (pintype "passive"))
      (node (ref "X6") (pin "9") (pinfunction "1_9") (pintype "passive"))
    )
    (net (code "7") (name "/A3_UART_TX") (class "Default")
      (node (ref "BUS1") (pin "3") (pinfunction "3_3") (pintype "passive"))
      (node (ref "LGP1-5") (pin "3") (pinfunction "3_3") (pintype "passive"))
      (node (ref "R72") (pin "1") (pinfunction "1_1") (pintype "passive"))
    )
    (net (code "8") (name "/A4_UART_RX") (class "Default")
      (node (ref "BUS1") (pin "1") (pinfunction "1_1") (pintype "passive"))
      (node (ref "LGP1-5") (pin "2") (pinfunction "2_2") (pintype "passive"))
    )
    (net (code "9") (name "/A5_OLED_CS") (class "Default")
      (node (ref "LGP1-5") (pin "1") (pinfunction "1_1") (pintype "passive"))
      (node (ref "X6") (pin "8") (pinfunction "1_8") (pintype "passive"))
    )
    (net (code "10") (name "/A6_TLC_GSCLK") (class "Default")
      (node (ref "LGP6-7") (pin "2") (pinfunction "2_2") (pintype "passive"))
      (node (ref "U3") (pin "25") (pinfunction "GSCLK_25") (pintype "bidirectional"))
      (node (ref "U7") (pin "25") (pinfunction "GSCLK_25") (pintype "bidirectional"))
      (node (ref "U8") (pin "25") (pinfunction "GSCLK_25") (pintype "bidirectional"))
    )
    (net (code "11") (name "/A7_ENC_CNG_RDY") (class "Default")
      (node (ref "LGP6-7") (pin "1") (pinfunction "1_1") (pintype "passive"))
      (node (ref "U2") (pin "9") (pinfunction "PA3_9") (pintype "bidirectional"))
    )
    (net (code "12") (name "/A12") (class "Default")
      (node (ref "ANG3") (pin "1") (pinfunction "1_1") (pintype "passive"))
    )
    (net (code "13") (name "/A13_ENC_NCS") (class "Default")
      (node (ref "ANG3") (pin "2") (pinfunction "2_2") (pintype "passive"))
      (node (ref "U2") (pin "10") (pinfunction "PA4_10") (pintype "bidirectional"))
    )
    (net (code "14") (name "/A14") (class "Default")
      (node (ref "ANG3") (pin "3") (pinfunction "3_3") (pintype "passive"))
    )
    (net (code "15") (name "/A16_I2C_SCL") (class "Default")
      (node (ref "ANG3") (pin "5") (pinfunction "5_5") (pintype "passive"))
      (node (ref "BUS2") (pin "1") (pinfunction "1_1") (pintype "passive"))
    )
    (net (code "16") (name "/A17_I2C_SDA") (class "Default")
      (node (ref "ANG3") (pin "6") (pinfunction "6_6") (pintype "passive"))
      (node (ref "BUS2") (pin "3") (pinfunction "3_3") (pintype "passive"))
    )
    (net (code "17") (name "/A22_PIXI_NCS") (class "Default")
      (node (ref "EXTSPI") (pin "4") (pinfunction "4_4") (pintype "passive"))
      (node (ref "U1") (pin "6") (pinfunction "~{CS}_6") (pintype "bidirectional"))
    )
    (net (code "18") (name "/A23_SPIA_CLK") (class "Default")
      (node (ref "EXTSPI") (pin "3") (pinfunction "3_3") (pintype "passive"))
      (node (ref "U1") (pin "5") (pinfunction "SCLK_5") (pintype "bidirectional"))
      (node (ref "U2") (pin "11") (pinfunction "PA5_11") (pintype "bidirectional"))
    )
    (net (code "19") (name "/A24_SPIA_MISO") (class "Default")
      (node (ref "EXTSPI") (pin "2") (pinfunction "2_2") (pintype "passive"))
      (node (ref "U1") (pin "7") (pinfunction "DOUT_7") (pintype "bidirectional"))
      (node (ref "U2") (pin "12") (pinfunction "PA6_12") (pintype "bidirectional"))
    )
    (net (code "20") (name "/A25_SPIA_MOSI") (class "Default")
      (node (ref "EXTSPI") (pin "1") (pinfunction "1_1") (pintype "passive"))
      (node (ref "U1") (pin "4") (pinfunction "DIN_4") (pintype "bidirectional"))
    )
    (net (code "21") (name "/AIN_A") (class "Default")
      (node (ref "ANG2") (pin "4") (pinfunction "4_4") (pintype "passive"))
      (node (ref "C9") (pin "1") (pinfunction "1_1") (pintype "passive"))
      (node (ref "R9") (pin "2") (pinfunction "2_2") (pintype "passive"))
    )
    (net (code "22") (name "/AIN_B") (class "Default")
      (node (ref "ANG2") (pin "3") (pinfunction "3_3") (pintype "passive"))
      (node (ref "C10") (pin "1") (pinfunction "1_1") (pintype "passive"))
      (node (ref "R8") (pin "2") (pinfunction "2_2") (pintype "passive"))
    )
    (net (code "23") (name "/AOUT_A+") (class "Default")
      (node (ref "ANG1") (pin "5") (pinfunction "5_5") (pintype "passive"))
      (node (ref "R2") (pin "2") (pinfunction "2_2") (pintype "passive"))
    )
    (net (code "24") (name "/AOUT_A-") (class "Default")
      (node (ref "ANG2") (pin "1") (pinfunction "1_1") (pintype "passive"))
      (node (ref "R1") (pin "2") (pinfunction "2_2") (pintype "passive"))
    )
    (net (code "25") (name "/AOUT_B+") (class "Default")
      (node (ref "ANG1") (pin "4") (pinfunction "4_4") (pintype "passive"))
      (node (ref "R11") (pin "2") (pinfunction "2_2") (pintype "passive"))
    )
    (net (code "26") (name "/AOUT_B-") (class "Default")
      (node (ref "ANG1") (pin "6") (pinfunction "6_6") (pintype "passive"))
      (node (ref "R10") (pin "2") (pinfunction "2_2") (pintype "passive"))
    )
    (net (code "27") (name "/B4_SPIB_MOSI") (class "Default")
      (node (ref "LGP6-1") (pin "2") (pinfunction "2_2") (pintype "passive"))
      (node (ref "U3") (pin "5") (pinfunction "SIN_5") (pintype "bidirectional"))
      (node (ref "X6") (pin "14") (pinfunction "1_14") (pintype "passive"))
    )
    (net (code "28") (name "/B5_SPIB_CLK") (class "Default")
      (node (ref "LGP6-1") (pin "1") (pinfunction "1_1") (pintype "passive"))
      (node (ref "U3") (pin "4") (pinfunction "SCLK_4") (pintype "bidirectional"))
      (node (ref "U7") (pin "4") (pinfunction "SCLK_4") (pintype "bidirectional"))
      (node (ref "U8") (pin "4") (pinfunction "SCLK_4") (pintype "bidirectional"))
      (node (ref "X6") (pin "13") (pinfunction "1_13") (pintype "passive"))
    )
    (net (code "29") (name "/B8_USBH_PWR_EN") (class "Default")
      (node (ref "R70") (pin "1") (pinfunction "1_1") (pintype "passive"))
      (node (ref "U9") (pin "3") (pinfunction "EN_3") (pintype "input"))
      (node (ref "USBH") (pin "5") (pinfunction "5_5") (pintype "passive"))
    )
    (net (code "30") (name "/B9_USBH_PWR_FAULT") (class "Default")
      (node (ref "U9") (pin "4") (pinfunction "FAULT_4") (pintype "output"))
      (node (ref "USBH") (pin "6") (pinfunction "6_6") (pintype "passive"))
    )
    (net (code "31") (name "/B12_TLC_BLANK") (class "Default")
      (node (ref "U3") (pin "2") (pinfunction "BLANK_2") (pintype "bidirectional"))
      (node (ref "U7") (pin "2") (pinfunction "BLANK_2") (pintype "bidirectional"))
      (node (ref "U8") (pin "2") (pinfunction "BLANK_2") (pintype "bidirectional"))
      (node (ref "USB1") (pin "1") (pinfunction "1_1") (pintype "passive"))
    )
    (net (code "32") (name "/B13_ENC_NRST") (class "Default")
      (node (ref "C21") (pin "2") (pinfunction "2_2") (pintype "passive"))
      (node (ref "U2") (pin "4") (pinfunction "NRST_4") (pintype "input"))
      (node (ref "USB1") (pin "2") (pinfunction "2_2") (pintype "passive"))
      (node (ref "X1") (pin "5") (pinfunction "S_5") (pintype "passive"))
    )
    (net (code "33") (name "/B14_TLC_XLAT") (class "Default")
      (node (ref "U3") (pin "3") (pinfunction "XLAT_3") (pintype "bidirectional"))
      (node (ref "U7") (pin "3") (pinfunction "XLAT_3") (pintype "bidirectional"))
      (node (ref "U8") (pin "3") (pinfunction "XLAT_3") (pintype "bidirectional"))
      (node (ref "USB1") (pin "3") (pinfunction "3_3") (pintype "passive"))
    )
    (net (code "34") (name "/B15_TLC_MODE") (class "Default")
      (node (ref "U3") (pin "6") (pinfunction "MODE_6") (pintype "bidirectional"))
      (node (ref "U7") (pin "6") (pinfunction "MODE_6") (pintype "bidirectional"))
      (node (ref "U8") (pin "6") (pinfunction "MODE_6") (pintype "bidirectional"))
      (node (ref "USB1") (pin "4") (pinfunction "4_4") (pintype "passive"))
    )
    (net (code "35") (name "/B16") (class "Default")
      (node (ref "USB1") (pin "5") (pinfunction "5_5") (pintype "passive"))
    )
    (net (code "36") (name "/BOOT") (class "Default")
      (node (ref "ANG3") (pin "4") (pinfunction "4_4") (pintype "passive"))
      (node (ref "BOOT") (pin "2") (pinfunction "2_2") (pintype "passive"))
    )
    (net (code "37") (name "/CS_VREF") (class "Default")
      (node (ref "ANG2") (pin "5") (pinfunction "5_5") (pintype "passive"))
      (node (ref "C10") (pin "2") (pinfunction "2_2") (pintype "passive"))
      (node (ref "C9") (pin "2") (pinfunction "2_2") (pintype "passive"))
      (node (ref "R19") (pin "1") (pinfunction "1_1") (pintype "passive"))
      (node (ref "R67") (pin "1") (pinfunction "1_1") (pintype "passive"))
    )
    (net (code "38") (name "/ENC1_A") (class "Default")
      (node (ref "C2") (pin "2") (pinfunction "2_2") (pintype "passive"))
      (node (ref "ENC1") (pin "PINA") (pinfunction "A_PINA") (pintype "bidirectional"))
      (node (ref "U2") (pin "18") (pinfunction "PA8_18") (pintype "bidirectional"))
    )
    (net (code "39") (name "/ENC1_B") (class "Default")
      (node (ref "C1") (pin "2") (pinfunction "2_2") (pintype "passive"))
      (node (ref "ENC1") (pin "PINB") (pinfunction "B_PINB") (pintype "bidirectional"))
      (node (ref "U2") (pin "19") (pinfunction "PA9_19") (pintype "bidirectional"))
    )
    (net (code "40") (name "/ENC1_SW") (class "Default")
      (node (ref "ENC1") (pin "SWITCH1") (pinfunction "P_SWITCH1") (pintype "passive"))
      (node (ref "U2") (pin "20") (pinfunction "PA10_20") (pintype "bidirectional"))
    )
    (net (code "41") (name "/ENC2_A") (class "Default")
      (node (ref "C4") (pin "2") (pinfunction "2_2") (pintype "passive"))
      (node (ref "ENC2") (pin "PINA") (pinfunction "A_PINA") (pintype "bidirectional"))
      (node (ref "U2") (pin "6") (pinfunction "PA0_6") (pintype "bidirectional"))
    )
    (net (code "42") (name "/ENC2_B") (class "Default")
      (node (ref "C3") (pin "2") (pinfunction "2_2") (pintype "passive"))
      (node (ref "ENC2") (pin "PINB") (pinfunction "B_PINB") (pintype "bidirectional"))
      (node (ref "U2") (pin "7") (pinfunction "PA1_7") (pintype "bidirectional"))
    )
    (net (code "43") (name "/ENC2_SW") (class "Default")
      (node (ref "ENC2") (pin "SWITCH1") (pinfunction "P_SWITCH1") (pintype "passive"))
      (node (ref "U2") (pin "8") (pinfunction "PA2_8") (pintype "bidirectional"))
    )
    (net (code "44") (name "/ENC3_A") (class "Default")
      (node (ref "C45") (pin "2") (pinfunction "2_2") (pintype "passive"))
      (node (ref "ENC3") (pin "PINA") (pinfunction "A_PINA") (pintype "bidirectional"))
      (node (ref "U2") (pin "21") (pinfunction "PA11_21") (pintype "bidirectional"))
    )
    (net (code "45") (name "/ENC3_B") (class "Default")
      (node (ref "C44") (pin "2") (pinfunction "2_2") (pintype "passive"))
      (node (ref "ENC3") (pin "PINB") (pinfunction "B_PINB") (pintype "bidirectional"))
      (node (ref "U2") (pin "22") (pinfunction "PA12_22") (pintype "bidirectional"))
    )
    (net (code "46") (name "/ENC3_SW") (class "Default")
      (node (ref "ENC3") (pin "SWITCH1") (pinfunction "P_SWITCH1") (pintype "passive"))
      (node (ref "U2") (pin "25") (pinfunction "PA15_25") (pintype "bidirectional"))
    )
    (net (code "47") (name "/ENC4_A") (class "Default")
      (node (ref "C70") (pin "2") (pinfunction "2_2") (pintype "passive"))
      (node (ref "ENC4") (pin "PINA") (pinfunction "A_PINA") (pintype "bidirectional"))
      (node (ref "U2") (pin "27") (pinfunction "PB4_27") (pintype "bidirectional"))
    )
    (net (code "48") (name "/ENC4_B") (class "Default")
      (node (ref "C46") (pin "2") (pinfunction "2_2") (pintype "passive"))
      (node (ref "ENC4") (pin "PINB") (pinfunction "B_PINB") (pintype "bidirectional"))
      (node (ref "U2") (pin "13") (pinfunction "PA7_13") (pintype "bidirectional"))
    )
    (net (code "49") (name "/ENC4_SW") (class "Default")
      (node (ref "ENC4") (pin "SWITCH1") (pinfunction "P_SWITCH1") (pintype "passive"))
      (node (ref "U2") (pin "26") (pinfunction "PB3_26") (pintype "bidirectional"))
    )
    (net (code "50") (name "/ENC5_A") (class "Default")
      (node (ref "C72") (pin "2") (pinfunction "2_2") (pintype "passive"))
      (node (ref "ENC5") (pin "PINA") (pinfunction "A_PINA") (pintype "bidirectional"))
      (node (ref "U2") (pin "28") (pinfunction "PB5_28") (pintype "bidirectional"))
    )
    (net (code "51") (name "/ENC5_B") (class "Default")
      (node (ref "C71") (pin "2") (pinfunction "2_2") (pintype "passive"))
      (node (ref "ENC5") (pin "PINB") (pinfunction "B_PINB") (pintype "bidirectional"))
      (node (ref "U2") (pin "29") (pinfunction "PB6_29") (pintype "bidirectional"))
    )
    (net (code "52") (name "/ENC5_SW") (class "Default")
      (node (ref "ENC5") (pin "SWITCH1") (pinfunction "P_SWITCH1") (pintype "passive"))
      (node (ref "U2") (pin "14") (pinfunction "PB0_14") (pintype "bidirectional"))
    )
    (net (code "53") (name "/ENC6_A") (class "Default")
      (node (ref "C74") (pin "2") (pinfunction "2_2") (pintype "passive"))
      (node (ref "ENC6") (pin "PINA") (pinfunction "A_PINA") (pintype "bidirectional"))
      (node (ref "U2") (pin "2") (pinfunction "PF0_2") (pintype "bidirectional"))
    )
    (net (code "54") (name "/ENC6_B") (class "Default")
      (node (ref "C73") (pin "2") (pinfunction "2_2") (pintype "passive"))
      (node (ref "ENC6") (pin "PINB") (pinfunction "B_PINB") (pintype "bidirectional"))
      (node (ref "U2") (pin "3") (pinfunction "PF1_3") (pintype "bidirectional"))
    )
    (net (code "55") (name "/ENC6_SW") (class "Default")
      (node (ref "ENC6") (pin "SWITCH1") (pinfunction "P_SWITCH1") (pintype "passive"))
      (node (ref "U2") (pin "30") (pinfunction "PB7_30") (pintype "bidirectional"))
    )
    (net (code "56") (name "/ENC_SWCLK") (class "Default")
      (node (ref "U2") (pin "24") (pinfunction "PA14_24") (pintype "bidirectional"))
      (node (ref "X1") (pin "2") (pinfunction "S_2") (pintype "passive"))
    )
    (net (code "57") (name "/ENC_SWDIO") (class "Default")
      (node (ref "U2") (pin "23") (pinfunction "PA13_23") (pintype "bidirectional"))
      (node (ref "X1") (pin "4") (pinfunction "S_4") (pintype "passive"))
    )
    (net (code "58") (name "/INL") (class "Default")
      (node (ref "INL") (pin "P$3") (pinfunction "3_P$3") (pintype "passive"))
      (node (ref "R22") (pin "1") (pinfunction "1_1") (pintype "passive"))
    )
    (net (code "59") (name "/INR") (class "Default")
      (node (ref "INR") (pin "P$3") (pinfunction "3_P$3") (pintype "passive"))
      (node (ref "R69") (pin "1") (pinfunction "1_1") (pintype "passive"))
    )
    (net (code "60") (name "/LED1_B") (class "Default")
      (node (ref "LED1") (pin "P1") (pinfunction "CRED_P1") (pintype "passive"))
      (node (ref "U8") (pin "8") (pinfunction "OUT1_8") (pintype "bidirectional"))
    )
    (net (code "61") (name "/LED1_G") (class "Default")
      (node (ref "LED1") (pin "P4") (pinfunction "CBLUE_P4") (pintype "passive"))
      (node (ref "U7") (pin "8") (pinfunction "OUT1_8") (pintype "bidirectional"))
    )
    (net (code "62") (name "/LED1_R") (class "Default")
      (node (ref "LED1") (pin "P2") (pinfunction "CGREEN_P2") (pintype "passive"))
      (node (ref "U3") (pin "8") (pinfunction "OUT1_8") (pintype "bidirectional"))
    )
    (net (code "63") (name "/LED2_B") (class "Default")
      (node (ref "LED2") (pin "P1") (pinfunction "CRED_P1") (pintype "passive"))
      (node (ref "U8") (pin "10") (pinfunction "OUT3_10") (pintype "bidirectional"))
    )
    (net (code "64") (name "/LED2_G") (class "Default")
      (node (ref "LED2") (pin "P4") (pinfunction "CBLUE_P4") (pintype "passive"))
      (node (ref "U7") (pin "10") (pinfunction "OUT3_10") (pintype "bidirectional"))
    )
    (net (code "65") (name "/LED2_R") (class "Default")
      (node (ref "LED2") (pin "P2") (pinfunction "CGREEN_P2") (pintype "passive"))
      (node (ref "U3") (pin "10") (pinfunction "OUT3_10") (pintype "bidirectional"))
    )
    (net (code "66") (name "/LED3_B") (class "Default")
      (node (ref "LED3") (pin "P1") (pinfunction "CRED_P1") (pintype "passive"))
      (node (ref "U8") (pin "13") (pinfunction "OUT6_13") (pintype "bidirectional"))
    )
    (net (code "67") (name "/LED3_G") (class "Default")
      (node (ref "LED3") (pin "P4") (pinfunction "CBLUE_P4") (pintype "passive"))
      (node (ref "U7") (pin "13") (pinfunction "OUT6_13") (pintype "bidirectional"))
    )
    (net (code "68") (name "/LED3_R") (class "Default")
      (node (ref "LED3") (pin "P2") (pinfunction "CGREEN_P2") (pintype "passive"))
      (node (ref "U3") (pin "12") (pinfunction "OUT5_12") (pintype "bidirectional"))
    )
    (net (code "69") (name "/LED4_B") (class "Default")
      (node (ref "LED4") (pin "P1") (pinfunction "CRED_P1") (pintype "passive"))
      (node (ref "U8") (pin "14") (pinfunction "OUT7_14") (pintype "bidirectional"))
    )
    (net (code "70") (name "/LED4_G") (class "Default")
      (node (ref "LED4") (pin "P4") (pinfunction "CBLUE_P4") (pintype "passive"))
      (node (ref "U7") (pin "14") (pinfunction "OUT7_14") (pintype "bidirectional"))
    )
    (net (code "71") (name "/LED4_R") (class "Default")
      (node (ref "LED4") (pin "P2") (pinfunction "CGREEN_P2") (pintype "passive"))
      (node (ref "U3") (pin "14") (pinfunction "OUT7_14") (pintype "bidirectional"))
    )
    (net (code "72") (name "/LED5_B") (class "Default")
      (node (ref "LED5") (pin "P1") (pinfunction "CRED_P1") (pintype "passive"))
      (node (ref "U8") (pin "15") (pinfunction "OUT8_15") (pintype "bidirectional"))
    )
    (net (code "73") (name "/LED5_G") (class "Default")
      (node (ref "LED5") (pin "P4") (pinfunction "CBLUE_P4") (pintype "passive"))
      (node (ref "U7") (pin "15") (pinfunction "OUT8_15") (pintype "bidirectional"))
    )
    (net (code "74") (name "/LED5_R") (class "Default")
      (node (ref "LED5") (pin "P2") (pinfunction "CGREEN_P2") (pintype "passive"))
      (node (ref "U3") (pin "15") (pinfunction "OUT8_15") (pintype "bidirectional"))
    )
    (net (code "75") (name "/LED6_B") (class "Default")
      (node (ref "LED6") (pin "P1") (pinfunction "CRED_P1") (pintype "passive"))
      (node (ref "U8") (pin "18") (pinfunction "OUT11_18") (pintype "bidirectional"))
    )
    (net (code "76") (name "/LED6_G") (class "Default")
      (node (ref "LED6") (pin "P4") (pinfunction "CBLUE_P4") (pintype "passive"))
      (node (ref "U7") (pin "18") (pinfunction "OUT11_18") (pintype "bidirectional"))
    )
    (net (code "77") (name "/LED6_R") (class "Default")
      (node (ref "LED6") (pin "P2") (pinfunction "CGREEN_P2") (pintype "passive"))
      (node (ref "U3") (pin "18") (pinfunction "OUT11_18") (pintype "bidirectional"))
    )
    (net (code "78") (name "/LED7_B") (class "Default")
      (node (ref "LED7") (pin "P1") (pinfunction "CRED_P1") (pintype "passive"))
      (node (ref "U8") (pin "20") (pinfunction "OUT13_20") (pintype "bidirectional"))
    )
    (net (code "79") (name "/LED7_G") (class "Default")
      (node (ref "LED7") (pin "P4") (pinfunction "CBLUE_P4") (pintype "passive"))
      (node (ref "U7") (pin "20") (pinfunction "OUT13_20") (pintype "bidirectional"))
    )
    (net (code "80") (name "/LED7_R") (class "Default")
      (node (ref "LED7") (pin "P2") (pinfunction "CGREEN_P2") (pintype "passive"))
      (node (ref "U3") (pin "20") (pinfunction "OUT13_20") (pintype "bidirectional"))
    )
    (net (code "81") (name "/LED8_B") (class "Default")
      (node (ref "LED8") (pin "P1") (pinfunction "CRED_P1") (pintype "passive"))
      (node (ref "U8") (pin "22") (pinfunction "OUT15_22") (pintype "bidirectional"))
    )
    (net (code "82") (name "/LED8_G") (class "Default")
      (node (ref "LED8") (pin "P4") (pinfunction "CBLUE_P4") (pintype "passive"))
      (node (ref "U7") (pin "22") (pinfunction "OUT15_22") (pintype "bidirectional"))
    )
    (net (code "83") (name "/LED8_R") (class "Default")
      (node (ref "LED8") (pin "P2") (pinfunction "CGREEN_P2") (pintype "passive"))
      (node (ref "U3") (pin "22") (pinfunction "OUT15_22") (pintype "bidirectional"))
    )
    (net (code "84") (name "/LED9_B") (class "Default")
      (node (ref "LED9") (pin "P1") (pinfunction "CRED_P1") (pintype "passive"))
      (node (ref "U8") (pin "7") (pinfunction "OUT0_7") (pintype "bidirectional"))
    )
    (net (code "85") (name "/LED9_G") (class "Default")
      (node (ref "LED9") (pin "P4") (pinfunction "CBLUE_P4") (pintype "passive"))
      (node (ref "U7") (pin "7") (pinfunction "OUT0_7") (pintype "bidirectional"))
    )
    (net (code "86") (name "/LED9_R") (class "Default")
      (node (ref "LED9") (pin "P2") (pinfunction "CGREEN_P2") (pintype "passive"))
      (node (ref "U3") (pin "7") (pinfunction "OUT0_7") (pintype "bidirectional"))
    )
    (net (code "87") (name "/LED10_B") (class "Default")
      (node (ref "LED10") (pin "P1") (pinfunction "CRED_P1") (pintype "passive"))
      (node (ref "U8") (pin "9") (pinfunction "OUT2_9") (pintype "bidirectional"))
    )
    (net (code "88") (name "/LED10_G") (class "Default")
      (node (ref "LED10") (pin "P4") (pinfunction "CBLUE_P4") (pintype "passive"))
      (node (ref "U7") (pin "9") (pinfunction "OUT2_9") (pintype "bidirectional"))
    )
    (net (code "89") (name "/LED10_R") (class "Default")
      (node (ref "LED10") (pin "P2") (pinfunction "CGREEN_P2") (pintype "passive"))
      (node (ref "U3") (pin "9") (pinfunction "OUT2_9") (pintype "bidirectional"))
    )
    (net (code "90") (name "/LED11_B") (class "Default")
      (node (ref "LED11") (pin "P1") (pinfunction "CRED_P1") (pintype "passive"))
      (node (ref "U8") (pin "11") (pinfunction "OUT4_11") (pintype "bidirectional"))
    )
    (net (code "91") (name "/LED11_G") (class "Default")
      (node (ref "LED11") (pin "P4") (pinfunction "CBLUE_P4") (pintype "passive"))
      (node (ref "U7") (pin "11") (pinfunction "OUT4_11") (pintype "bidirectional"))
    )
    (net (code "92") (name "/LED11_R") (class "Default")
      (node (ref "LED11") (pin "P2") (pinfunction "CGREEN_P2") (pintype "passive"))
      (node (ref "U3") (pin "11") (pinfunction "OUT4_11") (pintype "bidirectional"))
    )
    (net (code "93") (name "/LED12_B") (class "Default")
      (node (ref "LED12") (pin "P1") (pinfunction "CRED_P1") (pintype "passive"))
      (node (ref "U8") (pin "12") (pinfunction "OUT5_12") (pintype "bidirectional"))
    )
    (net (code "94") (name "/LED12_G") (class "Default")
      (node (ref "LED12") (pin "P4") (pinfunction "CBLUE_P4") (pintype "passive"))
      (node (ref "U7") (pin "12") (pinfunction "OUT5_12") (pintype "bidirectional"))
    )
    (net (code "95") (name "/LED12_R") (class "Default")
      (node (ref "LED12") (pin "P2") (pinfunction "CGREEN_P2") (pintype "passive"))
      (node (ref "U3") (pin "13") (pinfunction "OUT6_13") (pintype "bidirectional"))
    )
    (net (code "96") (name "/LED13_B") (class "Default")
      (node (ref "LED13") (pin "P1") (pinfunction "CRED_P1") (pintype "passive"))
      (node (ref "U8") (pin "16") (pinfunction "OUT9_16") (pintype "bidirectional"))
    )
    (net (code "97") (name "/LED13_G") (class "Default")
      (node (ref "LED13") (pin "P4") (pinfunction "CBLUE_P4") (pintype "passive"))
      (node (ref "U7") (pin "16") (pinfunction "OUT9_16") (pintype "bidirectional"))
    )
    (net (code "98") (name "/LED13_R") (class "Default")
      (node (ref "LED13") (pin "P2") (pinfunction "CGREEN_P2") (pintype "passive"))
      (node (ref "U3") (pin "16") (pinfunction "OUT9_16") (pintype "bidirectional"))
    )
    (net (code "99") (name "/LED14_B") (class "Default")
      (node (ref "LED14") (pin "P1") (pinfunction "CRED_P1") (pintype "passive"))
      (node (ref "U8") (pin "17") (pinfunction "OUT10_17") (pintype "bidirectional"))
    )
    (net (code "100") (name "/LED14_G") (class "Default")
      (node (ref "LED14") (pin "P4") (pinfunction "CBLUE_P4") (pintype "passive"))
      (node (ref "U7") (pin "17") (pinfunction "OUT10_17") (pintype "bidirectional"))
    )
    (net (code "101") (name "/LED14_R") (class "Default")
      (node (ref "LED14") (pin "P2") (pinfunction "CGREEN_P2") (pintype "passive"))
      (node (ref "U3") (pin "17") (pinfunction "OUT10_17") (pintype "bidirectional"))
    )
    (net (code "102") (name "/LED15_B") (class "Default")
      (node (ref "LED15") (pin "P1") (pinfunction "CRED_P1") (pintype "passive"))
      (node (ref "U8") (pin "19") (pinfunction "OUT12_19") (pintype "bidirectional"))
    )
    (net (code "103") (name "/LED15_G") (class "Default")
      (node (ref "LED15") (pin "P4") (pinfunction "CBLUE_P4") (pintype "passive"))
      (node (ref "U7") (pin "19") (pinfunction "OUT12_19") (pintype "bidirectional"))
    )
    (net (code "104") (name "/LED15_R") (class "Default")
      (node (ref "LED15") (pin "P2") (pinfunction "CGREEN_P2") (pintype "passive"))
      (node (ref "U3") (pin "19") (pinfunction "OUT12_19") (pintype "bidirectional"))
    )
    (net (code "105") (name "/LED16_B") (class "Default")
      (node (ref "LED16") (pin "P1") (pinfunction "CRED_P1") (pintype "passive"))
      (node (ref "U8") (pin "21") (pinfunction "OUT14_21") (pintype "bidirectional"))
    )
    (net (code "106") (name "/LED16_G") (class "Default")
      (node (ref "LED16") (pin "P4") (pinfunction "CBLUE_P4") (pintype "passive"))
      (node (ref "U7") (pin "21") (pinfunction "OUT14_21") (pintype "bidirectional"))
    )
    (net (code "107") (name "/LED16_R") (class "Default")
      (node (ref "LED16") (pin "P2") (pinfunction "CGREEN_P2") (pintype "passive"))
      (node (ref "U3") (pin "21") (pinfunction "OUT14_21") (pintype "bidirectional"))
    )
    (net (code "108") (name "/OUTL") (class "Default")
      (node (ref "OUTL") (pin "P$3") (pinfunction "3_P$3") (pintype "passive"))
      (node (ref "R16") (pin "1") (pinfunction "1_1") (pintype "passive"))
    )
    (net (code "109") (name "/OUTR") (class "Default")
      (node (ref "OUTR") (pin "P$3") (pinfunction "3_P$3") (pintype "passive"))
      (node (ref "R17") (pin "1") (pinfunction "1_1") (pintype "passive"))
    )
    (net (code "110") (name "/P1") (class "Default")
      (node (ref "P1") (pin "P$3") (pinfunction "3_P$3") (pintype "passive"))
      (node (ref "R23") (pin "1") (pinfunction "1_1") (pintype "passive"))
    )
    (net (code "111") (name "/P2") (class "Default")
      (node (ref "P2") (pin "P$3") (pinfunction "3_P$3") (pintype "passive"))
      (node (ref "R24") (pin "1") (pinfunction "1_1") (pintype "passive"))
    )
    (net (code "112") (name "/P3") (class "Default")
      (node (ref "P3") (pin "P$3") (pinfunction "3_P$3") (pintype "passive"))
      (node (ref "R25") (pin "1") (pinfunction "1_1") (pintype "passive"))
    )
    (net (code "113") (name "/P4") (class "Default")
      (node (ref "P4") (pin "P$3") (pinfunction "3_P$3") (pintype "passive"))
      (node (ref "R26") (pin "1") (pinfunction "1_1") (pintype "passive"))
    )
    (net (code "114") (name "/P5") (class "Default")
      (node (ref "P5") (pin "P$3") (pinfunction "3_P$3") (pintype "passive"))
      (node (ref "R27") (pin "1") (pinfunction "1_1") (pintype "passive"))
    )
    (net (code "115") (name "/P6") (class "Default")
      (node (ref "P6") (pin "P$3") (pinfunction "3_P$3") (pintype "passive"))
      (node (ref "R28") (pin "1") (pinfunction "1_1") (pintype "passive"))
    )
    (net (code "116") (name "/P7") (class "Default")
      (node (ref "P7") (pin "P$3") (pinfunction "3_P$3") (pintype "passive"))
      (node (ref "R29") (pin "1") (pinfunction "1_1") (pintype "passive"))
    )
    (net (code "117") (name "/P8") (class "Default")
      (node (ref "P8") (pin "P$3") (pinfunction "3_P$3") (pintype "passive"))
      (node (ref "R30") (pin "1") (pinfunction "1_1") (pintype "passive"))
    )
    (net (code "118") (name "/P9") (class "Default")
      (node (ref "P9") (pin "P$3") (pinfunction "3_P$3") (pintype "passive"))
      (node (ref "R31") (pin "1") (pinfunction "1_1") (pintype "passive"))
    )
    (net (code "119") (name "/P10") (class "Default")
      (node (ref "P10") (pin "P$3") (pinfunction "3_P$3") (pintype "passive"))
      (node (ref "R32") (pin "1") (pinfunction "1_1") (pintype "passive"))
    )
    (net (code "120") (name "/P11") (class "Default")
      (node (ref "P11") (pin "P$3") (pinfunction "3_P$3") (pintype "passive"))
      (node (ref "R33") (pin "1") (pinfunction "1_1") (pintype "passive"))
    )
    (net (code "121") (name "/P12") (class "Default")
      (node (ref "P12") (pin "P$3") (pinfunction "3_P$3") (pintype "passive"))
      (node (ref "R34") (pin "1") (pinfunction "1_1") (pintype "passive"))
    )
    (net (code "122") (name "/P13") (class "Default")
      (node (ref "P13") (pin "P$3") (pinfunction "3_P$3") (pintype "passive"))
      (node (ref "R35") (pin "1") (pinfunction "1_1") (pintype "passive"))
    )
    (net (code "123") (name "/P14") (class "Default")
      (node (ref "P14") (pin "P$3") (pinfunction "3_P$3") (pintype "passive"))
      (node (ref "R36") (pin "1") (pinfunction "1_1") (pintype "passive"))
    )
    (net (code "124") (name "/P15") (class "Default")
      (node (ref "P15") (pin "P$3") (pinfunction "3_P$3") (pintype "passive"))
      (node (ref "R37") (pin "1") (pinfunction "1_1") (pintype "passive"))
    )
    (net (code "125") (name "/P16") (class "Default")
      (node (ref "P16") (pin "P$3") (pinfunction "3_P$3") (pintype "passive"))
      (node (ref "R38") (pin "1") (pinfunction "1_1") (pintype "passive"))
    )
    (net (code "126") (name "/P17") (class "Default")
      (node (ref "P17") (pin "P$3") (pinfunction "3_P$3") (pintype "passive"))
      (node (ref "R21") (pin "1") (pinfunction "1_1") (pintype "passive"))
    )
    (net (code "127") (name "/P18") (class "Default")
      (node (ref "P18") (pin "P$3") (pinfunction "3_P$3") (pintype "passive"))
      (node (ref "R41") (pin "1") (pinfunction "1_1") (pintype "passive"))
    )
    (net (code "128") (name "/P19") (class "Default")
      (node (ref "P19") (pin "P$3") (pinfunction "3_P$3") (pintype "passive"))
      (node (ref "R42") (pin "1") (pinfunction "1_1") (pintype "passive"))
    )
    (net (code "129") (name "/P20") (class "Default")
      (node (ref "P20") (pin "P$3") (pinfunction "3_P$3") (pintype "passive"))
      (node (ref "R45") (pin "1") (pinfunction "1_1") (pintype "passive"))
    )
    (net (code "130") (name "/PORT0") (class "Default")
      (node (ref "C47") (pin "1") (pinfunction "1_1") (pintype "passive"))
      (node (ref "R23") (pin "2") (pinfunction "2_2") (pintype "passive"))
      (node (ref "U1") (pin "27") (pinfunction "PORT4_27") (pintype "bidirectional"))
    )
    (net (code "131") (name "/PORT1") (class "Default")
      (node (ref "C48") (pin "1") (pinfunction "1_1") (pintype "passive"))
      (node (ref "R24") (pin "2") (pinfunction "2_2") (pintype "passive"))
      (node (ref "U1") (pin "31") (pinfunction "PORT7_31") (pintype "bidirectional"))
    )
    (net (code "132") (name "/PORT2") (class "Default")
      (node (ref "C49") (pin "1") (pinfunction "1_1") (pintype "passive"))
      (node (ref "R25") (pin "2") (pinfunction "2_2") (pintype "passive"))
      (node (ref "U1") (pin "32") (pinfunction "PORT8_32") (pintype "bidirectional"))
    )
    (net (code "133") (name "/PORT3") (class "Default")
      (node (ref "C50") (pin "1") (pinfunction "1_1") (pintype "passive"))
      (node (ref "R26") (pin "2") (pinfunction "2_2") (pintype "passive"))
      (node (ref "U1") (pin "36") (pinfunction "PORT11_36") (pintype "bidirectional"))
    )
    (net (code "134") (name "/PORT4") (class "Default")
      (node (ref "C51") (pin "1") (pinfunction "1_1") (pintype "passive"))
      (node (ref "R27") (pin "2") (pinfunction "2_2") (pintype "passive"))
      (node (ref "U1") (pin "37") (pinfunction "PORT12_37") (pintype "bidirectional"))
    )
    (net (code "135") (name "/PORT5") (class "Default")
      (node (ref "C52") (pin "1") (pinfunction "1_1") (pintype "passive"))
      (node (ref "R28") (pin "2") (pinfunction "2_2") (pintype "passive"))
      (node (ref "U1") (pin "43") (pinfunction "PORT15_43") (pintype "bidirectional"))
    )
    (net (code "136") (name "/PORT6") (class "Default")
      (node (ref "C53") (pin "1") (pinfunction "1_1") (pintype "passive"))
      (node (ref "R29") (pin "2") (pinfunction "2_2") (pintype "passive"))
      (node (ref "U1") (pin "45") (pinfunction "PORT16_45") (pintype "bidirectional"))
    )
    (net (code "137") (name "/PORT7") (class "Default")
      (node (ref "C54") (pin "1") (pinfunction "1_1") (pintype "passive"))
      (node (ref "R30") (pin "2") (pinfunction "2_2") (pintype "passive"))
      (node (ref "U1") (pin "1") (pinfunction "PORT19_1") (pintype "bidirectional"))
    )
    (net (code "138") (name "/PORT8") (class "Default")
      (node (ref "C62") (pin "1") (pinfunction "1_1") (pintype "passive"))
      (node (ref "R38") (pin "2") (pinfunction "2_2") (pintype "passive"))
      (node (ref "U1") (pin "47") (pinfunction "PORT18_47") (pintype "bidirectional"))
    )
    (net (code "139") (name "/PORT9") (class "Default")
      (node (ref "C61") (pin "1") (pinfunction "1_1") (pintype "passive"))
      (node (ref "R37") (pin "2") (pinfunction "2_2") (pintype "passive"))
      (node (ref "U1") (pin "46") (pinfunction "PORT17_46") (pintype "bidirectional"))
    )
    (net (code "140") (name "/PORT10") (class "Default")
      (node (ref "C60") (pin "1") (pinfunction "1_1") (pintype "passive"))
      (node (ref "R36") (pin "2") (pinfunction "2_2") (pintype "passive"))
      (node (ref "U1") (pin "42") (pinfunction "PORT14_42") (pintype "bidirectional"))
    )
    (net (code "141") (name "/PORT11") (class "Default")
      (node (ref "C59") (pin "1") (pinfunction "1_1") (pintype "passive"))
      (node (ref "R35") (pin "2") (pinfunction "2_2") (pintype "passive"))
      (node (ref "U1") (pin "40") (pinfunction "PORT13_40") (pintype "bidirectional"))
    )
    (net (code "142") (name "/PORT12") (class "Default")
      (node (ref "C58") (pin "1") (pinfunction "1_1") (pintype "passive"))
      (node (ref "R34") (pin "2") (pinfunction "2_2") (pintype "passive"))
      (node (ref "U1") (pin "35") (pinfunction "PORT10_35") (pintype "bidirectional"))
    )
    (net (code "143") (name "/PORT13") (class "Default")
      (node (ref "C57") (pin "1") (pinfunction "1_1") (pintype "passive"))
      (node (ref "R33") (pin "2") (pinfunction "2_2") (pintype "passive"))
      (node (ref "U1") (pin "33") (pinfunction "PORT9_33") (pintype "bidirectional"))
    )
    (net (code "144") (name "/PORT14") (class "Default")
      (node (ref "C56") (pin "1") (pinfunction "1_1") (pintype "passive"))
      (node (ref "R32") (pin "2") (pinfunction "2_2") (pintype "passive"))
      (node (ref "U1") (pin "30") (pinfunction "PORT6_30") (pintype "bidirectional"))
    )
    (net (code "145") (name "/PORT15") (class "Default")
      (node (ref "C55") (pin "1") (pinfunction "1_1") (pintype "passive"))
      (node (ref "R31") (pin "2") (pinfunction "2_2") (pintype "passive"))
      (node (ref "U1") (pin "28") (pinfunction "PORT5_28") (pintype "bidirectional"))
    )
    (net (code "146") (name "/PORT16") (class "Default")
      (node (ref "C78") (pin "1") (pinfunction "1_1") (pintype "passive"))
      (node (ref "R45") (pin "2") (pinfunction "2_2") (pintype "passive"))
      (node (ref "U1") (pin "19") (pinfunction "PORT0_19") (pintype "bidirectional"))
    )
    (net (code "147") (name "/PORT17") (class "Default")
      (node (ref "C77") (pin "1") (pinfunction "1_1") (pintype "passive"))
      (node (ref "R42") (pin "2") (pinfunction "2_2") (pintype "passive"))
      (node (ref "U1") (pin "20") (pinfunction "PORT1_20") (pintype "bidirectional"))
    )
    (net (code "148") (name "/PORT18") (class "Default")
      (node (ref "C76") (pin "1") (pinfunction "1_1") (pintype "passive"))
      (node (ref "R41") (pin "2") (pinfunction "2_2") (pintype "passive"))
      (node (ref "U1") (pin "21") (pinfunction "PORT2_21") (pintype "bidirectional"))
    )
    (net (code "149") (name "/PORT19") (class "Default")
      (node (ref "C75") (pin "1") (pinfunction "1_1") (pintype "passive"))
      (node (ref "R21") (pin "2") (pinfunction "2_2") (pintype "passive"))
      (node (ref "U1") (pin "25") (pinfunction "PORT3_25") (pintype "bidirectional"))
    )
    (net (code "150") (name "/USBD_DM") (class "Default")
      (node (ref "EXT") (pin "4") (pinfunction "4_4") (pintype "passive"))
      (node (ref "USBD") (pin "3") (pinfunction "3_3") (pintype "passive"))
    )
    (net (code "151") (name "/USBD_DP") (class "Default")
      (node (ref "EXT") (pin "6") (pinfunction "6_6") (pintype "passive"))
      (node (ref "USBD") (pin "2") (pinfunction "2_2") (pintype "passive"))
    )
    (net (code "152") (name "/USBD_ID") (class "Default")
      (node (ref "USBD") (pin "1") (pinfunction "1_1") (pintype "passive"))
    )
    (net (code "153") (name "/USBD_VBUS") (class "Default")
      (node (ref "EXT") (pin "2") (pinfunction "2_2") (pintype "passive"))
      (node (ref "USBD") (pin "4") (pinfunction "4_4") (pintype "passive"))
    )
    (net (code "154") (name "/USBH_DM") (class "Default")
      (node (ref "EXT") (pin "3") (pinfunction "3_3") (pintype "passive"))
      (node (ref "USBH") (pin "1") (pinfunction "1_1") (pintype "passive"))
    )
    (net (code "155") (name "/USBH_DP") (class "Default")
      (node (ref "EXT") (pin "5") (pinfunction "5_5") (pintype "passive"))
      (node (ref "USBH") (pin "2") (pinfunction "2_2") (pintype "passive"))
    )
    (net (code "156") (name "/USBH_ID") (class "Default")
      (node (ref "USBH") (pin "3") (pinfunction "3_3") (pintype "passive"))
    )
    (net (code "157") (name "/USBH_VBUS") (class "Default")
      (node (ref "EXT") (pin "1") (pinfunction "1_1") (pintype "passive"))
      (node (ref "U9") (pin "6") (pinfunction "VOUT_6") (pintype "output"))
      (node (ref "USBH") (pin "4") (pinfunction "4_4") (pintype "passive"))
    )
    (net (code "158") (name "/VSUP") (class "Default")
      (node (ref "C29") (pin "1") (pinfunction "1_1") (pintype "passive"))
      (node (ref "CON_PWR") (pin "P1") (pinfunction "-1_P1") (pintype "bidirectional"))
      (node (ref "U4") (pin "VIN") (pinfunction "VIN_VIN") (pintype "input"))
      (node (ref "VSUP") (pin "2") (pinfunction "2_2") (pintype "passive"))
    )
    (net (code "159") (name "GND") (class "Default")
      (node (ref "ANG1") (pin "2") (pinfunction "2_2") (pintype "passive"))
      (node (ref "AUDIO_IN") (pin "2") (pinfunction "2_2") (pintype "passive"))
      (node (ref "AUDIO_OUT") (pin "2") (pinfunction "2_2") (pintype "passive"))
      (node (ref "BUS1") (pin "2") (pinfunction "2_2") (pintype "passive"))
      (node (ref "BUS2") (pin "2") (pinfunction "2_2") (pintype "passive"))
      (node (ref "BUS3") (pin "2") (pinfunction "2_2") (pintype "passive"))
      (node (ref "C1") (pin "1") (pinfunction "1_1") (pintype "passive"))
      (node (ref "C101") (pin "-") (pinfunction "-_-") (pintype "passive"))
      (node (ref "C11") (pin "2") (pinfunction "2_2") (pintype "passive"))
      (node (ref "C12") (pin "2") (pinfunction "2_2") (pintype "passive"))
      (node (ref "C13") (pin "1") (pinfunction "1_1") (pintype "passive"))
      (node (ref "C14") (pin "2") (pinfunction "2_2") (pintype "passive"))
      (node (ref "C16") (pin "2") (pinfunction "2_2") (pintype "passive"))
      (node (ref "C17") (pin "2") (pinfunction "2_2") (pintype "passive"))
      (node (ref "C18") (pin "2") (pinfunction "2_2") (pintype "passive"))
      (node (ref "C19") (pin "2") (pinfunction "2_2") (pintype "passive"))
      (node (ref "C2") (pin "1") (pinfunction "1_1") (pintype "passive"))
      (node (ref "C20") (pin "2") (pinfunction "2_2") (pintype "passive"))
      (node (ref "C23") (pin "1") (pinfunction "1_1") (pintype "passive"))
      (node (ref "C24") (pin "+") (pinfunction "+_+") (pintype "passive"))
      (node (ref "C26") (pin "-") (pinfunction "-_-") (pintype "passive"))
      (node (ref "C27") (pin "2") (pinfunction "2_2") (pintype "passive"))
      (node (ref "C28") (pin "-") (pinfunction "-_-") (pintype "passive"))
      (node (ref "C29") (pin "2") (pinfunction "2_2") (pintype "passive"))
      (node (ref "C3") (pin "1") (pinfunction "1_1") (pintype "passive"))
      (node (ref "C32") (pin "2") (pinfunction "2_2") (pintype "passive"))
      (node (ref "C33") (pin "2") (pinfunction "2_2") (pintype "passive"))
      (node (ref "C34") (pin "2") (pinfunction "2_2") (pintype "passive"))
      (node (ref "C4") (pin "1") (pinfunction "1_1") (pintype "passive"))
      (node (ref "C44") (pin "1") (pinfunction "1_1") (pintype "passive"))
      (node (ref "C45") (pin "1") (pinfunction "1_1") (pintype "passive"))
      (node (ref "C46") (pin "1") (pinfunction "1_1") (pintype "passive"))
      (node (ref "C47") (pin "2") (pinfunction "2_2") (pintype "passive"))
      (node (ref "C48") (pin "2") (pinfunction "2_2") (pintype "passive"))
      (node (ref "C49") (pin "2") (pinfunction "2_2") (pintype "passive"))
      (node (ref "C5") (pin "1") (pinfunction "1_1") (pintype "passive"))
      (node (ref "C50") (pin "2") (pinfunction "2_2") (pintype "passive"))
      (node (ref "C51") (pin "2") (pinfunction "2_2") (pintype "passive"))
      (node (ref "C52") (pin "2") (pinfunction "2_2") (pintype "passive"))
      (node (ref "C53") (pin "2") (pinfunction "2_2") (pintype "passive"))
      (node (ref "C54") (pin "2") (pinfunction "2_2") (pintype "passive"))
      (node (ref "C55") (pin "2") (pinfunction "2_2") (pintype "passive"))
      (node (ref "C56") (pin "2") (pinfunction "2_2") (pintype "passive"))
      (node (ref "C57") (pin "2") (pinfunction "2_2") (pintype "passive"))
      (node (ref "C58") (pin "2") (pinfunction "2_2") (pintype "passive"))
      (node (ref "C59") (pin "2") (pinfunction "2_2") (pintype "passive"))
      (node (ref "C6") (pin "2") (pinfunction "2_2") (pintype "passive"))
      (node (ref "C60") (pin "2") (pinfunction "2_2") (pintype "passive"))
      (node (ref "C61") (pin "2") (pinfunction "2_2") (pintype "passive"))
      (node (ref "C62") (pin "2") (pinfunction "2_2") (pintype "passive"))
      (node (ref "C63") (pin "2") (pinfunction "2_2") (pintype "passive"))
      (node (ref "C64") (pin "2") (pinfunction "2_2") (pintype "passive"))
      (node (ref "C65") (pin "2") (pinfunction "2_2") (pintype "passive"))
      (node (ref "C66") (pin "2") (pinfunction "2_2") (pintype "passive"))
      (node (ref "C67") (pin "2") (pinfunction "2_2") (pintype "passive"))
      (node (ref "C68") (pin "2") (pinfunction "2_2") (pintype "passive"))
      (node (ref "C69") (pin "1") (pinfunction "1_1") (pintype "passive"))
      (node (ref "C70") (pin "1") (pinfunction "1_1") (pintype "passive"))
      (node (ref "C71") (pin "1") (pinfunction "1_1") (pintype "passive"))
      (node (ref "C72") (pin "1") (pinfunction "1_1") (pintype "passive"))
      (node (ref "C73") (pin "1") (pinfunction "1_1") (pintype "passive"))
      (node (ref "C74") (pin "1") (pinfunction "1_1") (pintype "passive"))
      (node (ref "C75") (pin "2") (pinfunction "2_2") (pintype "passive"))
      (node (ref "C76") (pin "2") (pinfunction "2_2") (pintype "passive"))
      (node (ref "C77") (pin "2") (pinfunction "2_2") (pintype "passive"))
      (node (ref "C78") (pin "2") (pinfunction "2_2") (pintype "passive"))
      (node (ref "C79") (pin "1") (pinfunction "1_1") (pintype "passive"))
      (node (ref "C8") (pin "2") (pinfunction "2_2") (pintype "passive"))
      (node (ref "C80") (pin "1") (pinfunction "1_1") (pintype "passive"))
      (node (ref "C81") (pin "C") (pinfunction "-_C") (pintype "passive"))
      (node (ref "C82") (pin "1") (pinfunction "1_1") (pintype "passive"))
      (node (ref "C83") (pin "1") (pinfunction "1_1") (pintype "passive"))
      (node (ref "CON_PWR") (pin "P2") (pinfunction "-2_P2") (pintype "bidirectional"))
      (node (ref "CON_PWR") (pin "P4") (pinfunction "-4_P4") (pintype "bidirectional"))
      (node (ref "ENC1") (pin "C") (pinfunction "C_C") (pintype "bidirectional"))
      (node (ref "ENC1") (pin "P$1") (pinfunction "P$1_P$1") (pintype "bidirectional"))
      (node (ref "ENC1") (pin "P$2") (pinfunction "P$1_P$2") (pintype "bidirectional"))
      (node (ref "ENC1") (pin "SWITCH2") (pinfunction "S_SWITCH2") (pintype "passive"))
      (node (ref "ENC2") (pin "C") (pinfunction "C_C") (pintype "bidirectional"))
      (node (ref "ENC2") (pin "P$1") (pinfunction "P$1_P$1") (pintype "bidirectional"))
      (node (ref "ENC2") (pin "P$2") (pinfunction "P$1_P$2") (pintype "bidirectional"))
      (node (ref "ENC2") (pin "SWITCH2") (pinfunction "S_SWITCH2") (pintype "passive"))
      (node (ref "ENC3") (pin "C") (pinfunction "C_C") (pintype "bidirectional"))
      (node (ref "ENC3") (pin "P$1") (pinfunction "P$1_P$1") (pintype "bidirectional"))
      (node (ref "ENC3") (pin "P$2") (pinfunction "P$1_P$2") (pintype "bidirectional"))
      (node (ref "ENC3") (pin "SWITCH2") (pinfunction "S_SWITCH2") (pintype "passive"))
      (node (ref "ENC4") (pin "C") (pinfunction "C_C") (pintype "bidirectional"))
      (node (ref "ENC4") (pin "P$1") (pinfunction "P$1_P$1") (pintype "bidirectional"))
      (node (ref "ENC4") (pin "P$2") (pinfunction "P$1_P$2") (pintype "bidirectional"))
      (node (ref "ENC4") (pin "SWITCH2") (pinfunction "S_SWITCH2") (pintype "passive"))
      (node (ref "ENC5") (pin "C") (pinfunction "C_C") (pintype "bidirectional"))
      (node (ref "ENC5") (pin "P$1") (pinfunction "P$1_P$1") (pintype "bidirectional"))
      (node (ref "ENC5") (pin "P$2") (pinfunction "P$1_P$2") (pintype "bidirectional"))
      (node (ref "ENC5") (pin "SWITCH2") (pinfunction "S_SWITCH2") (pintype "passive"))
      (node (ref "ENC6") (pin "C") (pinfunction "C_C") (pintype "bidirectional"))
      (node (ref "ENC6") (pin "P$1") (pinfunction "P$1_P$1") (pintype "bidirectional"))
      (node (ref "ENC6") (pin "P$2") (pinfunction "P$1_P$2") (pintype "bidirectional"))
      (node (ref "ENC6") (pin "SWITCH2") (pinfunction "S_SWITCH2") (pintype "passive"))
      (node (ref "EXT") (pin "7") (pinfunction "7_7") (pintype "passive"))
      (node (ref "EXT") (pin "8") (pinfunction "8_8") (pintype "passive"))
      (node (ref "INL") (pin "P$1") (pinfunction "5_P$1") (pintype "passive"))
      (node (ref "INL") (pin "P$2") (pinfunction "4_P$2") (pintype "passive"))
      (node (ref "INR") (pin "P$1") (pinfunction "5_P$1") (pintype "passive"))
      (node (ref "INR") (pin "P$2") (pinfunction "4_P$2") (pintype "passive"))
      (node (ref "J1") (pin "1") (pinfunction "1_1") (pintype "passive"))
      (node (ref "J2") (pin "1") (pinfunction "1_1") (pintype "passive"))
      (node (ref "J3") (pin "1") (pinfunction "1_1") (pintype "passive"))
      (node (ref "J4") (pin "1") (pinfunction "1_1") (pintype "passive"))
      (node (ref "J5") (pin "1") (pinfunction "1_1") (pintype "passive"))
      (node (ref "J6") (pin "1") (pinfunction "1_1") (pintype "passive"))
      (node (ref "JP2") (pin "3") (pinfunction "3_3") (pintype "passive"))
      (node (ref "JP2") (pin "4") (pinfunction "4_4") (pintype "passive"))
      (node (ref "JP2") (pin "5") (pinfunction "5_5") (pintype "passive"))
      (node (ref "JP2") (pin "6") (pinfunction "6_6") (pintype "passive"))
      (node (ref "JP2") (pin "7") (pinfunction "7_7") (pintype "passive"))
      (node (ref "JP2") (pin "8") (pinfunction "8_8") (pintype "passive"))
      (node (ref "OUTL") (pin "P$1") (pinfunction "5_P$1") (pintype "passive"))
      (node (ref "OUTR") (pin "P$1") (pinfunction "5_P$1") (pintype "passive"))
      (node (ref "P1") (pin "P$1") (pinfunction "5_P$1") (pintype "passive"))
      (node (ref "P10") (pin "P$1") (pinfunction "5_P$1") (pintype "passive"))
      (node (ref "P11") (pin "P$1") (pinfunction "5_P$1") (pintype "passive"))
      (node (ref "P12") (pin "P$1") (pinfunction "5_P$1") (pintype "passive"))
      (node (ref "P13") (pin "P$1") (pinfunction "5_P$1") (pintype "passive"))
      (node (ref "P14") (pin "P$1") (pinfunction "5_P$1") (pintype "passive"))
      (node (ref "P15") (pin "P$1") (pinfunction "5_P$1") (pintype "passive"))
      (node (ref "P16") (pin "P$1") (pinfunction "5_P$1") (pintype "passive"))
      (node (ref "P17") (pin "P$1") (pinfunction "5_P$1") (pintype "passive"))
      (node (ref "P18") (pin "P$1") (pinfunction "5_P$1") (pintype "passive"))
      (node (ref "P19") (pin "P$1") (pinfunction "5_P$1") (pintype "passive"))
      (node (ref "P2") (pin "P$1") (pinfunction "5_P$1") (pintype "passive"))
      (node (ref "P20") (pin "P$1") (pinfunction "5_P$1") (pintype "passive"))
      (node (ref "P3") (pin "P$1") (pinfunction "5_P$1") (pintype "passive"))
      (node (ref "P4") (pin "P$1") (pinfunction "5_P$1") (pintype "passive"))
      (node (ref "P5") (pin "P$1") (pinfunction "5_P$1") (pintype "passive"))
      (node (ref "P6") (pin "P$1") (pinfunction "5_P$1") (pintype "passive"))
      (node (ref "P7") (pin "P$1") (pinfunction "5_P$1") (pintype "passive"))
      (node (ref "P8") (pin "P$1") (pinfunction "5_P$1") (pintype "passive"))
      (node (ref "P9") (pin "P$1") (pinfunction "5_P$1") (pintype "passive"))
      (node (ref "PWR") (pin "2") (pinfunction "2_2") (pintype "passive"))
      (node (ref "Q3") (pin "1") (pinfunction "G_1") (pintype "passive"))
      (node (ref "Q4") (pin "1") (pinfunction "G_1") (pintype "passive"))
      (node (ref "R14") (pin "2") (pinfunction "2_2") (pintype "passive"))
      (node (ref "R20") (pin "2") (pinfunction "2_2") (pintype "passive"))
      (node (ref "R39") (pin "2") (pinfunction "2_2") (pintype "passive"))
      (node (ref "R40") (pin "2") (pinfunction "2_2") (pintype "passive"))
      (node (ref "R43") (pin "2") (pinfunction "2_2") (pintype "passive"))
      (node (ref "R44") (pin "1") (pinfunction "1_1") (pintype "passive"))
      (node (ref "R46") (pin "2") (pinfunction "2_2") (pintype "passive"))
      (node (ref "R47") (pin "2") (pinfunction "2_2") (pintype "passive"))
      (node (ref "R48") (pin "2") (pinfunction "2_2") (pintype "passive"))
      (node (ref "R49") (pin "2") (pinfunction "2_2") (pintype "passive"))
      (node (ref "R5") (pin "1") (pinfunction "1_1") (pintype "passive"))
      (node (ref "R50") (pin "2") (pinfunction "2_2") (pintype "passive"))
      (node (ref "R51") (pin "2") (pinfunction "2_2") (pintype "passive"))
      (node (ref "R52") (pin "2") (pinfunction "2_2") (pintype "passive"))
      (node (ref "R53") (pin "2") (pinfunction "2_2") (pintype "passive"))
      (node (ref "R54") (pin "2") (pinfunction "2_2") (pintype "passive"))
      (node (ref "R55") (pin "2") (pinfunction "2_2") (pintype "passive"))
      (node (ref "R56") (pin "2") (pinfunction "2_2") (pintype "passive"))
      (node (ref "R57") (pin "2") (pinfunction "2_2") (pintype "passive"))
      (node (ref "R58") (pin "2") (pinfunction "2_2") (pintype "passive"))
      (node (ref "R59") (pin "2") (pinfunction "2_2") (pintype "passive"))
      (node (ref "R6") (pin "2") (pinfunction "2_2") (pintype "passive"))
      (node (ref "R60") (pin "2") (pinfunction "2_2") (pintype "passive"))
      (node (ref "R61") (pin "2") (pinfunction "2_2") (pintype "passive"))
      (node (ref "R62") (pin "2") (pinfunction "2_2") (pintype "passive"))
      (node (ref "R63") (pin "2") (pinfunction "2_2") (pintype "passive"))
      (node (ref "R64") (pin "2") (pinfunction "2_2") (pintype "passive"))
      (node (ref "R65") (pin "2") (pinfunction "2_2") (pintype "passive"))
      (node (ref "R68") (pin "2") (pinfunction "2_2") (pintype "passive"))
      (node (ref "R70") (pin "2") (pinfunction "2_2") (pintype "passive"))
      (node (ref "U1") (pin "17") (pinfunction "AGND_17") (pintype "bidirectional"))
      (node (ref "U1") (pin "18") (pinfunction "AGND_18") (pintype "bidirectional"))
      (node (ref "U1") (pin "2") (pinfunction "DGND_2") (pintype "bidirectional"))
      (node (ref "U1") (pin "38") (pinfunction "AGND_38") (pintype "bidirectional"))
      (node (ref "U1") (pin "EP") (pinfunction "AGND_EP") (pintype "bidirectional"))
      (node (ref "U2") (pin "16") (pinfunction "VSS1_16") (pintype "power_in"))
      (node (ref "U2") (pin "32") (pinfunction "VSS2_32") (pintype "power_in"))
      (node (ref "U3") (pin "1") (pinfunction "GND_1") (pintype "bidirectional"))
      (node (ref "U4") (pin "GND") (pinfunction "GND_GND") (pintype "power_in"))
      (node (ref "U7") (pin "1") (pinfunction "GND_1") (pintype "bidirectional"))
      (node (ref "U8") (pin "1") (pinfunction "GND_1") (pintype "bidirectional"))
      (node (ref "U9") (pin "2") (pinfunction "GND_2") (pintype "power_in"))
      (node (ref "USBD") (pin "5") (pinfunction "5_5") (pintype "passive"))
      (node (ref "X1") (pin "3") (pinfunction "S_3") (pintype "passive"))
      (node (ref "X6") (pin "1") (pinfunction "1_1") (pintype "passive"))
      (node (ref "X6") (pin "11") (pinfunction "1_11") (pintype "passive"))
      (node (ref "X6") (pin "12") (pinfunction "1_12") (pintype "passive"))
      (node (ref "X6") (pin "16") (pinfunction "1_16") (pintype "passive"))
      (node (ref "X6") (pin "17") (pinfunction "1_17") (pintype "passive"))
      (node (ref "X6") (pin "18") (pinfunction "1_18") (pintype "passive"))
      (node (ref "X6") (pin "19") (pinfunction "1_19") (pintype "passive"))
      (node (ref "X6") (pin "2") (pinfunction "1_2") (pintype "passive"))
      (node (ref "X6") (pin "20") (pinfunction "1_20") (pintype "passive"))
      (node (ref "X6") (pin "24") (pinfunction "1_24") (pintype "passive"))
      (node (ref "X6") (pin "3") (pinfunction "1_3") (pintype "passive"))
      (node (ref "X6") (pin "6") (pinfunction "1_6") (pintype "passive"))
      (node (ref "X6") (pin "7") (pinfunction "1_7") (pintype "passive"))
    )
    (net (code "160") (name "Net-(AUDIO_OUT-Pad1)") (class "Default")
      (node (ref "AUDIO_OUT") (pin "1") (pinfunction "1_1") (pintype "passive"))
      (node (ref "R73") (pin "1") (pinfunction "1_1") (pintype "passive"))
    )
    (net (code "161") (name "Net-(AUDIO_OUT-Pad3)") (class "Default")
      (node (ref "AUDIO_OUT") (pin "3") (pinfunction "3_3") (pintype "passive"))
      (node (ref "R74") (pin "1") (pinfunction "1_1") (pintype "passive"))
    )
    (net (code "162") (name "Net-(BUS3-Pad1)") (class "Default")
      (node (ref "BUS3") (pin "1") (pinfunction "1_1") (pintype "passive"))
      (node (ref "R72") (pin "2") (pinfunction "2_2") (pintype "passive"))
    )
    (net (code "163") (name "Net-(BUS3-Pad3)") (class "Default")
      (node (ref "BUS3") (pin "3") (pinfunction "3_3") (pintype "passive"))
      (node (ref "R71") (pin "2") (pinfunction "2_2") (pintype "passive"))
    )
    (net (code "164") (name "Net-(C5-Pad2)") (class "Default")
      (node (ref "C5") (pin "2") (pinfunction "2_2") (pintype "passive"))
      (node (ref "R1") (pin "1") (pinfunction "1_1") (pintype "passive"))
      (node (ref "R3") (pin "2") (pinfunction "2_2") (pintype "passive"))
      (node (ref "R7") (pin "2") (pinfunction "2_2") (pintype "passive"))
    )
    (net (code "165") (name "Net-(C6-Pad1)") (class "Default")
      (node (ref "C6") (pin "1") (pinfunction "1_1") (pintype "passive"))
      (node (ref "R2") (pin "1") (pinfunction "1_1") (pintype "passive"))
      (node (ref "R4") (pin "2") (pinfunction "2_2") (pintype "passive"))
      (node (ref "R6") (pin "1") (pinfunction "1_1") (pintype "passive"))
    )
    (net (code "166") (name "Net-(C13-Pad2)") (class "Default")
      (node (ref "C13") (pin "2") (pinfunction "2_2") (pintype "passive"))
      (node (ref "R10") (pin "1") (pinfunction "1_1") (pintype "passive"))
      (node (ref "R12") (pin "2") (pinfunction "2_2") (pintype "passive"))
      (node (ref "R15") (pin "2") (pinfunction "2_2") (pintype "passive"))
    )
    (net (code "167") (name "Net-(C14-Pad1)") (class "Default")
      (node (ref "C14") (pin "1") (pinfunction "1_1") (pintype "passive"))
      (node (ref "R11") (pin "1") (pinfunction "1_1") (pintype "passive"))
      (node (ref "R13") (pin "2") (pinfunction "2_2") (pintype "passive"))
      (node (ref "R14") (pin "1") (pinfunction "1_1") (pintype "passive"))
    )
    (net (code "168") (name "Net-(C81-+)") (class "Default")
      (node (ref "C81") (pin "A") (pinfunction "+_A") (pintype "passive"))
      (node (ref "X6") (pin "22") (pinfunction "1_22") (pintype "passive"))
    )
    (net (code "169") (name "Net-(IC1A-+IN)") (class "Default")
      (node (ref "C8") (pin "1") (pinfunction "1_1") (pintype "passive"))
      (node (ref "IC1") (pin "3") (pinfunction "+IN_3") (pintype "input"))
      (node (ref "R4") (pin "1") (pinfunction "1_1") (pintype "passive"))
    )
    (net (code "170") (name "Net-(IC1A--IN)") (class "Default")
      (node (ref "C7") (pin "1") (pinfunction "1_1") (pintype "passive"))
      (node (ref "IC1") (pin "2") (pinfunction "-IN_2") (pintype "input"))
      (node (ref "R3") (pin "1") (pinfunction "1_1") (pintype "passive"))
    )
    (net (code "171") (name "Net-(IC1A-OUT)") (class "Default")
      (node (ref "C7") (pin "2") (pinfunction "2_2") (pintype "passive"))
      (node (ref "IC1") (pin "1") (pinfunction "OUT_1") (pintype "output"))
      (node (ref "R16") (pin "2") (pinfunction "2_2") (pintype "passive"))
      (node (ref "R7") (pin "1") (pinfunction "1_1") (pintype "passive"))
      (node (ref "R73") (pin "2") (pinfunction "2_2") (pintype "passive"))
    )
    (net (code "172") (name "Net-(IC1B-+IN)") (class "Default")
      (node (ref "C16") (pin "1") (pinfunction "1_1") (pintype "passive"))
      (node (ref "IC1") (pin "5") (pinfunction "+IN_5") (pintype "input"))
      (node (ref "R13") (pin "1") (pinfunction "1_1") (pintype "passive"))
    )
    (net (code "173") (name "Net-(IC1B--IN)") (class "Default")
      (node (ref "C15") (pin "1") (pinfunction "1_1") (pintype "passive"))
      (node (ref "IC1") (pin "6") (pinfunction "-IN_6") (pintype "input"))
      (node (ref "R12") (pin "1") (pinfunction "1_1") (pintype "passive"))
    )
    (net (code "174") (name "Net-(IC1B-OUT)") (class "Default")
      (node (ref "C15") (pin "2") (pinfunction "2_2") (pintype "passive"))
      (node (ref "IC1") (pin "7") (pinfunction "OUT_7") (pintype "output"))
      (node (ref "R15") (pin "1") (pinfunction "1_1") (pintype "passive"))
      (node (ref "R17") (pin "2") (pinfunction "2_2") (pintype "passive"))
      (node (ref "R74") (pin "2") (pinfunction "2_2") (pintype "passive"))
    )
    (net (code "175") (name "Net-(IC2A-+IN)") (class "Default")
      (node (ref "IC2") (pin "3") (pinfunction "+IN_3") (pintype "input"))
      (node (ref "R19") (pin "2") (pinfunction "2_2") (pintype "passive"))
      (node (ref "R20") (pin "1") (pinfunction "1_1") (pintype "passive"))
    )
    (net (code "176") (name "Net-(IC2A--IN)") (class "Default")
      (node (ref "AUDIO_IN") (pin "1") (pinfunction "1_1") (pintype "passive"))
      (node (ref "C22") (pin "1") (pinfunction "1_1") (pintype "passive"))
      (node (ref "IC2") (pin "2") (pinfunction "-IN_2") (pintype "input"))
      (node (ref "R18") (pin "1") (pinfunction "1_1") (pintype "passive"))
      (node (ref "R22") (pin "2") (pinfunction "2_2") (pintype "passive"))
    )
    (net (code "177") (name "Net-(IC2A-OUT)") (class "Default")
      (node (ref "C22") (pin "2") (pinfunction "2_2") (pintype "passive"))
      (node (ref "IC2") (pin "1") (pinfunction "OUT_1") (pintype "output"))
      (node (ref "R18") (pin "2") (pinfunction "2_2") (pintype "passive"))
      (node (ref "R9") (pin "1") (pinfunction "1_1") (pintype "passive"))
    )
    (net (code "178") (name "Net-(IC2B-+IN)") (class "Default")
      (node (ref "IC2") (pin "5") (pinfunction "+IN_5") (pintype "input"))
      (node (ref "R67") (pin "2") (pinfunction "2_2") (pintype "passive"))
      (node (ref "R68") (pin "1") (pinfunction "1_1") (pintype "passive"))
    )
    (net (code "179") (name "Net-(IC2B--IN)") (class "Default")
      (node (ref "AUDIO_IN") (pin "3") (pinfunction "3_3") (pintype "passive"))
      (node (ref "C25") (pin "1") (pinfunction "1_1") (pintype "passive"))
      (node (ref "IC2") (pin "6") (pinfunction "-IN_6") (pintype "input"))
      (node (ref "R66") (pin "1") (pinfunction "1_1") (pintype "passive"))
      (node (ref "R69") (pin "2") (pinfunction "2_2") (pintype "passive"))
    )
    (net (code "180") (name "Net-(IC2B-OUT)") (class "Default")
      (node (ref "C25") (pin "2") (pinfunction "2_2") (pintype "passive"))
      (node (ref "IC2") (pin "7") (pinfunction "OUT_7") (pintype "output"))
      (node (ref "R66") (pin "2") (pinfunction "2_2") (pintype "passive"))
      (node (ref "R8") (pin "1") (pinfunction "1_1") (pintype "passive"))
    )
    (net (code "181") (name "Net-(P1-4)") (class "Default")
      (node (ref "P1") (pin "P$2") (pinfunction "4_P$2") (pintype "passive"))
      (node (ref "R50") (pin "1") (pinfunction "1_1") (pintype "passive"))
    )
    (net (code "182") (name "Net-(P2-4)") (class "Default")
      (node (ref "P2") (pin "P$2") (pinfunction "4_P$2") (pintype "passive"))
      (node (ref "R51") (pin "1") (pinfunction "1_1") (pintype "passive"))
    )
    (net (code "183") (name "Net-(P3-4)") (class "Default")
      (node (ref "P3") (pin "P$2") (pinfunction "4_P$2") (pintype "passive"))
      (node (ref "R52") (pin "1") (pinfunction "1_1") (pintype "passive"))
    )
    (net (code "184") (name "Net-(P4-4)") (class "Default")
      (node (ref "P4") (pin "P$2") (pinfunction "4_P$2") (pintype "passive"))
      (node (ref "R53") (pin "1") (pinfunction "1_1") (pintype "passive"))
    )
    (net (code "185") (name "Net-(P5-4)") (class "Default")
      (node (ref "P5") (pin "P$2") (pinfunction "4_P$2") (pintype "passive"))
      (node (ref "R54") (pin "1") (pinfunction "1_1") (pintype "passive"))
    )
    (net (code "186") (name "Net-(P6-4)") (class "Default")
      (node (ref "P6") (pin "P$2") (pinfunction "4_P$2") (pintype "passive"))
      (node (ref "R55") (pin "1") (pinfunction "1_1") (pintype "passive"))
    )
    (net (code "187") (name "Net-(P7-4)") (class "Default")
      (node (ref "P7") (pin "P$2") (pinfunction "4_P$2") (pintype "passive"))
      (node (ref "R56") (pin "1") (pinfunction "1_1") (pintype "passive"))
    )
    (net (code "188") (name "Net-(P8-4)") (class "Default")
      (node (ref "P8") (pin "P$2") (pinfunction "4_P$2") (pintype "passive"))
      (node (ref "R57") (pin "1") (pinfunction "1_1") (pintype "passive"))
    )
    (net (code "189") (name "Net-(P9-4)") (class "Default")
      (node (ref "P9") (pin "P$2") (pinfunction "4_P$2") (pintype "passive"))
      (node (ref "R65") (pin "1") (pinfunction "1_1") (pintype "passive"))
    )
    (net (code "190") (name "Net-(P10-4)") (class "Default")
      (node (ref "P10") (pin "P$2") (pinfunction "4_P$2") (pintype "passive"))
      (node (ref "R64") (pin "1") (pinfunction "1_1") (pintype "passive"))
    )
    (net (code "191") (name "Net-(P11-4)") (class "Default")
      (node (ref "P11") (pin "P$2") (pinfunction "4_P$2") (pintype "passive"))
      (node (ref "R63") (pin "1") (pinfunction "1_1") (pintype "passive"))
    )
    (net (code "192") (name "Net-(P12-4)") (class "Default")
      (node (ref "P12") (pin "P$2") (pinfunction "4_P$2") (pintype "passive"))
      (node (ref "R62") (pin "1") (pinfunction "1_1") (pintype "passive"))
    )
    (net (code "193") (name "Net-(P13-4)") (class "Default")
      (node (ref "P13") (pin "P$2") (pinfunction "4_P$2") (pintype "passive"))
      (node (ref "R61") (pin "1") (pinfunction "1_1") (pintype "passive"))
    )
    (net (code "194") (name "Net-(P14-4)") (class "Default")
      (node (ref "P14") (pin "P$2") (pinfunction "4_P$2") (pintype "passive"))
      (node (ref "R60") (pin "1") (pinfunction "1_1") (pintype "passive"))
    )
    (net (code "195") (name "Net-(P15-4)") (class "Default")
      (node (ref "P15") (pin "P$2") (pinfunction "4_P$2") (pintype "passive"))
      (node (ref "R59") (pin "1") (pinfunction "1_1") (pintype "passive"))
    )
    (net (code "196") (name "Net-(P16-4)") (class "Default")
      (node (ref "P16") (pin "P$2") (pinfunction "4_P$2") (pintype "passive"))
      (node (ref "R58") (pin "1") (pinfunction "1_1") (pintype "passive"))
    )
    (net (code "197") (name "Net-(P17-4)") (class "Default")
      (node (ref "P17") (pin "P$2") (pinfunction "4_P$2") (pintype "passive"))
      (node (ref "R49") (pin "1") (pinfunction "1_1") (pintype "passive"))
    )
    (net (code "198") (name "Net-(P18-4)") (class "Default")
      (node (ref "P18") (pin "P$2") (pinfunction "4_P$2") (pintype "passive"))
      (node (ref "R48") (pin "1") (pinfunction "1_1") (pintype "passive"))
    )
    (net (code "199") (name "Net-(P19-4)") (class "Default")
      (node (ref "P19") (pin "P$2") (pinfunction "4_P$2") (pintype "passive"))
      (node (ref "R46") (pin "1") (pinfunction "1_1") (pintype "passive"))
    )
    (net (code "200") (name "Net-(P20-4)") (class "Default")
      (node (ref "P20") (pin "P$2") (pinfunction "4_P$2") (pintype "passive"))
      (node (ref "R47") (pin "1") (pinfunction "1_1") (pintype "passive"))
    )
    (net (code "201") (name "Net-(Q3-D)") (class "Default")
      (node (ref "JP2") (pin "1") (pinfunction "1_1") (pintype "passive"))
      (node (ref "JP2") (pin "2") (pinfunction "2_2") (pintype "passive"))
      (node (ref "Q3") (pin "3") (pinfunction "D_3") (pintype "passive"))
    )
    (net (code "202") (name "Net-(Q4-D)") (class "Default")
      (node (ref "JP2") (pin "10") (pinfunction "10_10") (pintype "passive"))
      (node (ref "JP2") (pin "9") (pinfunction "9_9") (pintype "passive"))
      (node (ref "Q4") (pin "3") (pinfunction "D_3") (pintype "passive"))
    )
    (net (code "203") (name "Net-(U1C-ADC_EXT_REF)") (class "Default")
      (node (ref "C33") (pin "1") (pinfunction "1_1") (pintype "passive"))
      (node (ref "U1") (pin "11") (pinfunction "ADC_EXT_REF_11") (pintype "bidirectional"))
    )
    (net (code "204") (name "Net-(U1C-ADC_INT_REF)") (class "Default")
      (node (ref "C34") (pin "1") (pinfunction "1_1") (pintype "passive"))
      (node (ref "U1") (pin "10") (pinfunction "ADC_INT_REF_10") (pintype "bidirectional"))
    )
    (net (code "205") (name "Net-(U1C-DAC_REF)") (class "Default")
      (node (ref "C32") (pin "1") (pinfunction "1_1") (pintype "passive"))
      (node (ref "U1") (pin "12") (pinfunction "DAC_REF_12") (pintype "bidirectional"))
    )
    (net (code "206") (name "Net-(U2-BOOT)") (class "Default")
      (node (ref "R5") (pin "2") (pinfunction "2_2") (pintype "passive"))
      (node (ref "U2") (pin "31") (pinfunction "BOOT_31") (pintype "input"))
    )
    (net (code "207") (name "Net-(U3-IREF)") (class "Default")
      (node (ref "R43") (pin "1") (pinfunction "1_1") (pintype "passive"))
      (node (ref "U3") (pin "27") (pinfunction "IREF_27") (pintype "bidirectional"))
    )
    (net (code "208") (name "Net-(U3-SOUT)") (class "Default")
      (node (ref "U3") (pin "24") (pinfunction "SOUT_24") (pintype "bidirectional"))
      (node (ref "U7") (pin "5") (pinfunction "SIN_5") (pintype "bidirectional"))
    )
    (net (code "209") (name "Net-(U7-IREF)") (class "Default")
      (node (ref "R39") (pin "1") (pinfunction "1_1") (pintype "passive"))
      (node (ref "U7") (pin "27") (pinfunction "IREF_27") (pintype "bidirectional"))
    )
    (net (code "210") (name "Net-(U7-SOUT)") (class "Default")
      (node (ref "U7") (pin "24") (pinfunction "SOUT_24") (pintype "bidirectional"))
      (node (ref "U8") (pin "5") (pinfunction "SIN_5") (pintype "bidirectional"))
    )
    (net (code "211") (name "Net-(U8-IREF)") (class "Default")
      (node (ref "R40") (pin "1") (pinfunction "1_1") (pintype "passive"))
      (node (ref "U8") (pin "27") (pinfunction "IREF_27") (pintype "bidirectional"))
    )
    (net (code "212") (name "Net-(X6N-1)") (class "Default")
      (node (ref "R44") (pin "2") (pinfunction "2_2") (pintype "passive"))
      (node (ref "X6") (pin "21") (pinfunction "1_21") (pintype "passive"))
    )
    (net (code "213") (name "unconnected-(ANG2-Pad2)") (class "Default")
      (node (ref "ANG2") (pin "2") (pinfunction "2_2") (pintype "passive"))
    )
    (net (code "214") (name "unconnected-(OUTL-4-PadP$2)") (class "Default")
      (node (ref "OUTL") (pin "P$2") (pinfunction "4_P$2") (pintype "passive"))
    )
    (net (code "215") (name "unconnected-(OUTR-4-PadP$2)") (class "Default")
      (node (ref "OUTR") (pin "P$2") (pinfunction "4_P$2") (pintype "passive"))
    )
    (net (code "216") (name "unconnected-(U1D-~{CNVT}-Pad9)") (class "Default")
      (node (ref "U1") (pin "9") (pinfunction "~{CNVT}_9") (pintype "bidirectional"))
    )
    (net (code "217") (name "unconnected-(U1D-~{INT}-Pad8)") (class "Default")
      (node (ref "U1") (pin "8") (pinfunction "~{INT}_8") (pintype "bidirectional"))
    )
    (net (code "218") (name "unconnected-(U1E-D0N-Pad14)") (class "Default")
      (node (ref "U1") (pin "14") (pinfunction "D0N_14") (pintype "bidirectional"))
    )
    (net (code "219") (name "unconnected-(U1E-D0P-Pad13)") (class "Default")
      (node (ref "U1") (pin "13") (pinfunction "D0P_13") (pintype "bidirectional"))
    )
    (net (code "220") (name "unconnected-(U1E-D1N-Pad23)") (class "Default")
      (node (ref "U1") (pin "23") (pinfunction "D1N_23") (pintype "bidirectional"))
    )
    (net (code "221") (name "unconnected-(U1E-D1P-Pad22)") (class "Default")
      (node (ref "U1") (pin "22") (pinfunction "D1P_22") (pintype "bidirectional"))
    )
    (net (code "222") (name "unconnected-(U2-PB1-Pad15)") (class "Default")
      (node (ref "U2") (pin "15") (pinfunction "PB1_15") (pintype "bidirectional"))
    )
    (net (code "223") (name "unconnected-(U3-XERR-Pad23)") (class "Default")
      (node (ref "U3") (pin "23") (pinfunction "XERR_23") (pintype "bidirectional"))
    )
    (net (code "224") (name "unconnected-(U7-XERR-Pad23)") (class "Default")
      (node (ref "U7") (pin "23") (pinfunction "XERR_23") (pintype "bidirectional"))
    )
    (net (code "225") (name "unconnected-(U8-SOUT-Pad24)") (class "Default")
      (node (ref "U8") (pin "24") (pinfunction "SOUT_24") (pintype "bidirectional"))
    )
    (net (code "226") (name "unconnected-(U8-XERR-Pad23)") (class "Default")
      (node (ref "U8") (pin "23") (pinfunction "XERR_23") (pintype "bidirectional"))
    )
    (net (code "227") (name "unconnected-(X6G-1-Pad15)") (class "Default")
      (node (ref "X6") (pin "15") (pinfunction "1_15") (pintype "passive"))
    )
    (net (code "228") (name "unconnected-(X6S-1-Pad4)") (class "Default")
      (node (ref "X6") (pin "4") (pinfunction "1_4") (pintype "passive"))
    )
  )
)
